# DNVT_box4rt.net
KiCad netlist of a schematic drawn in EAGLE
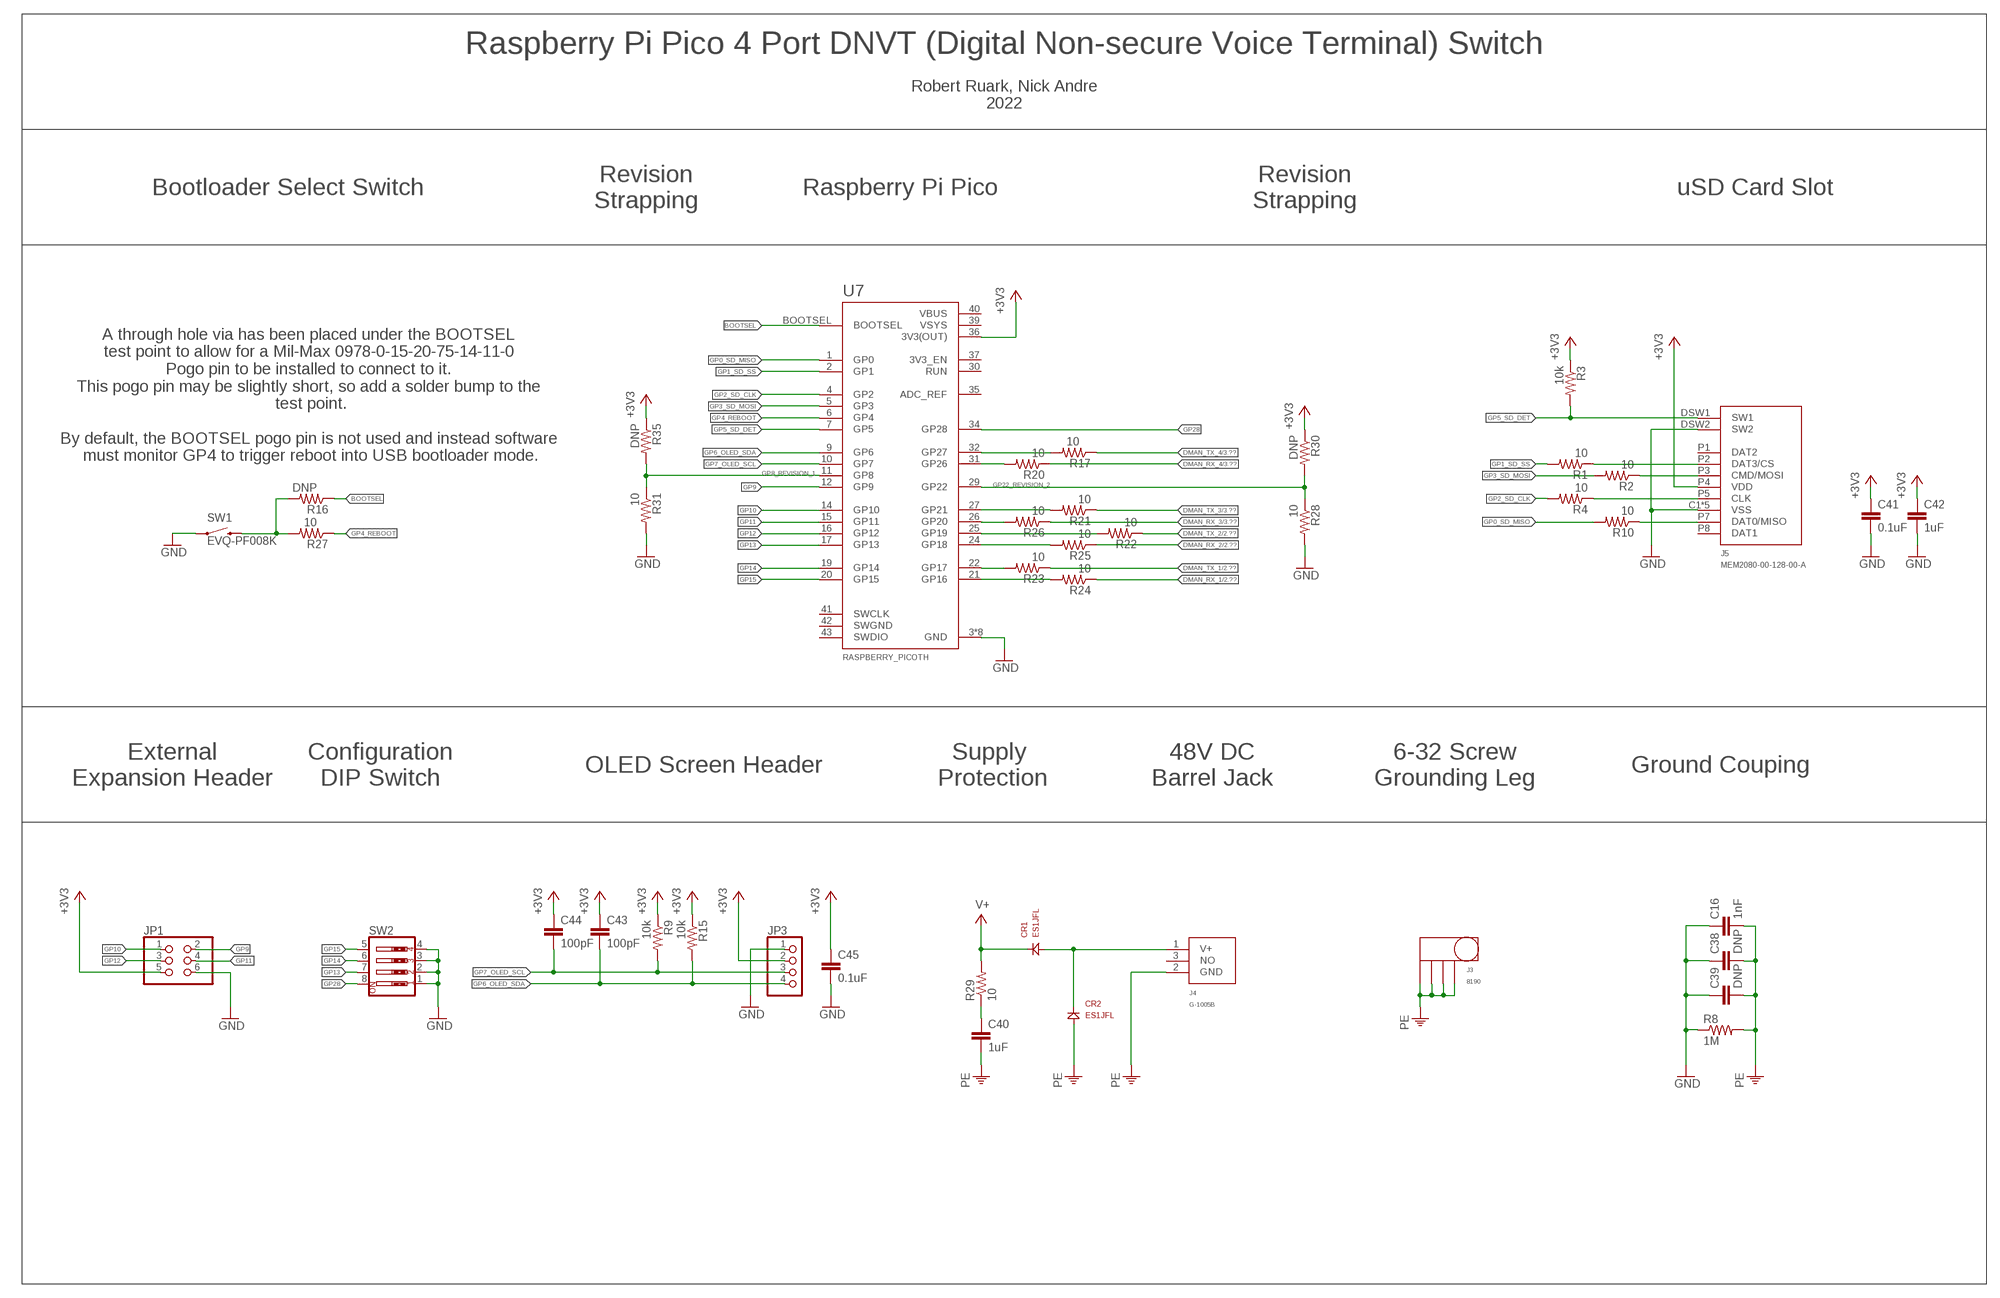
[diagram p0: schematic, sheet 1]
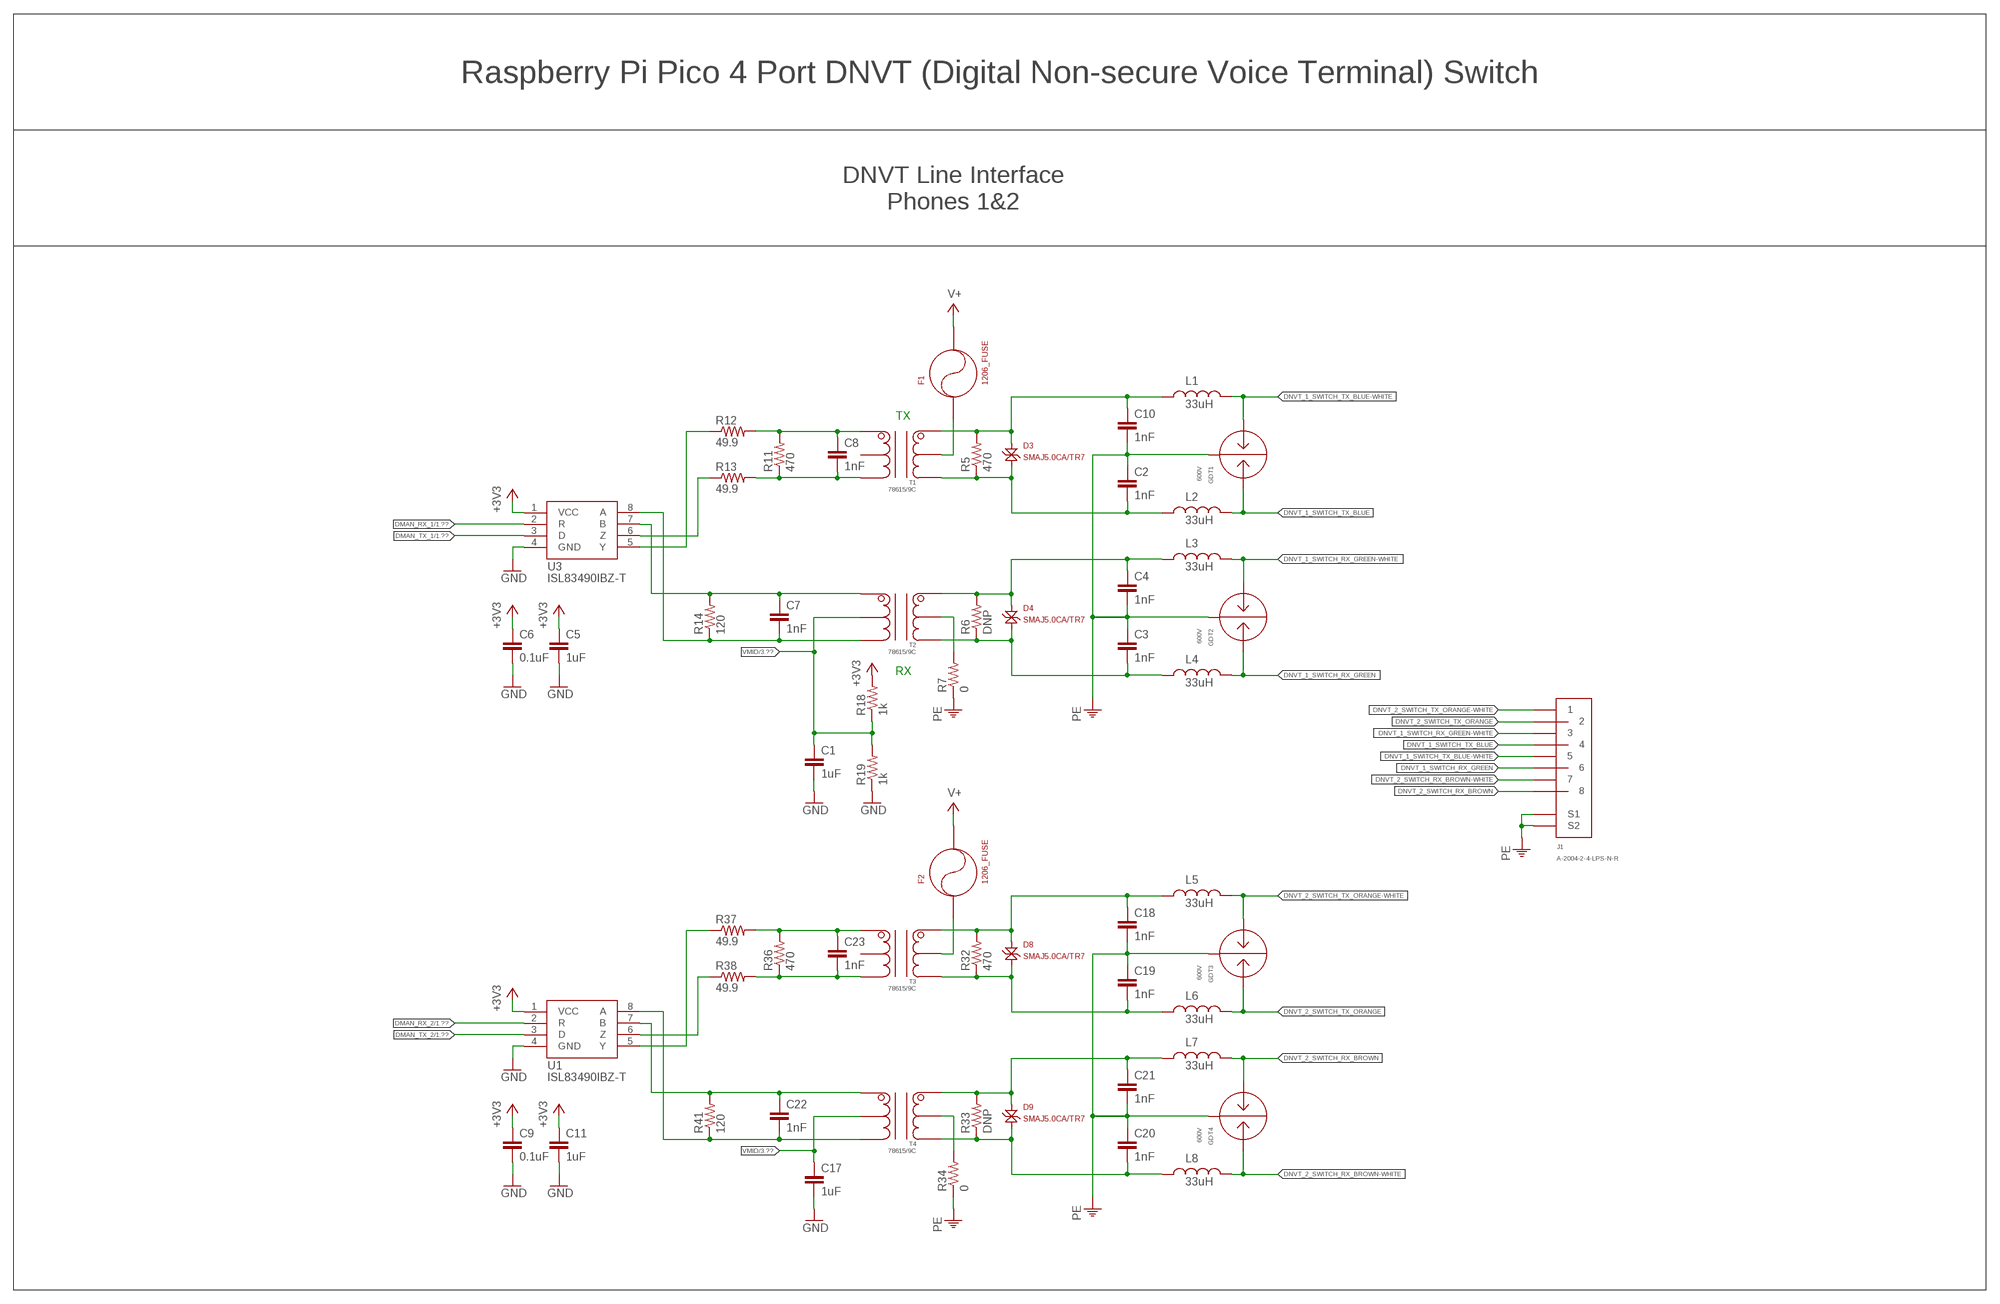
[diagram p1: schematic, sheet 2]
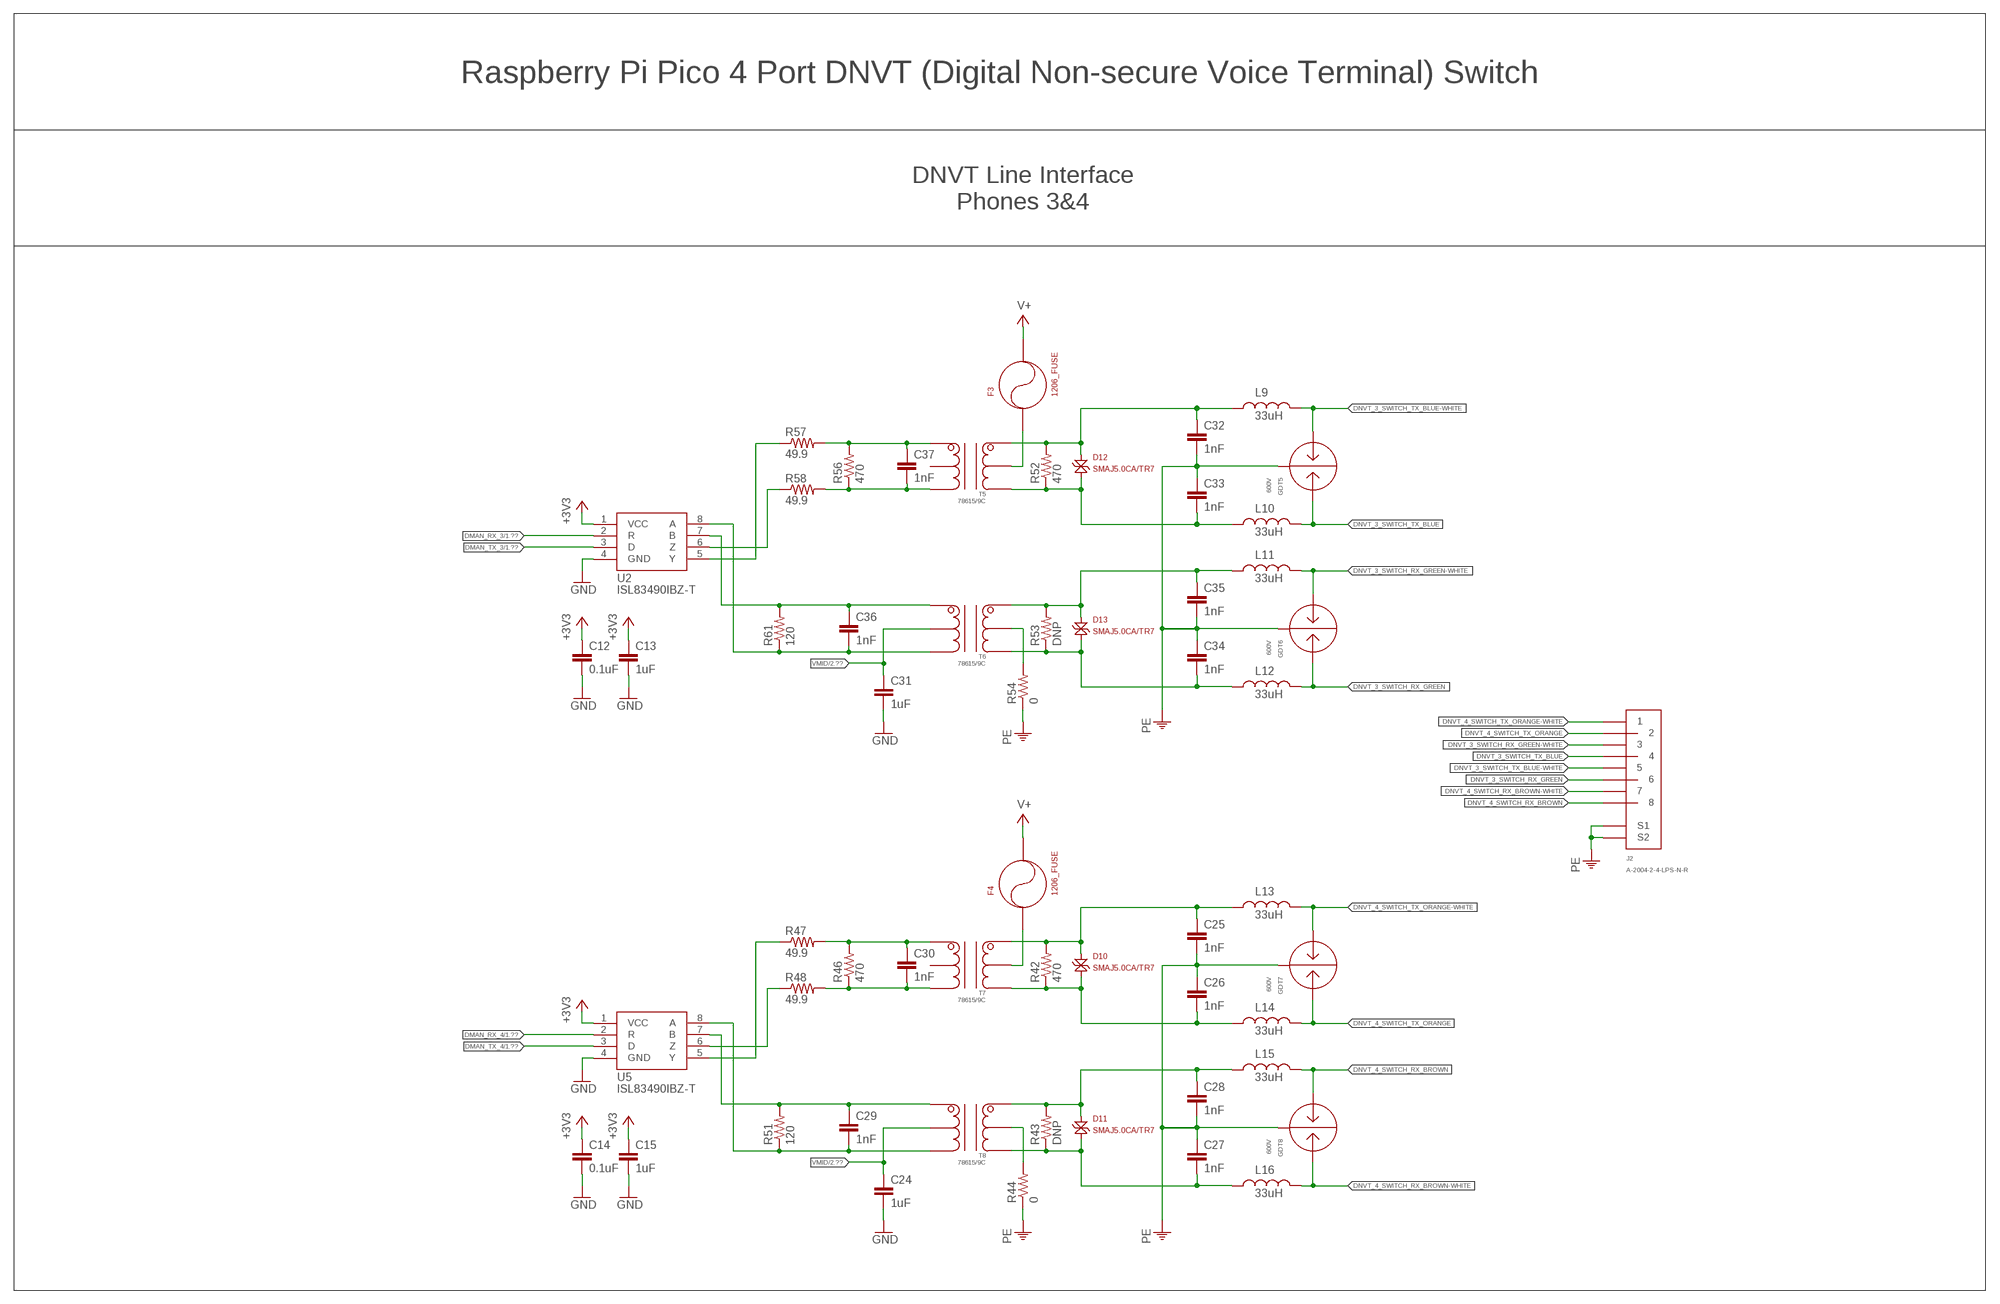
[diagram p2: schematic, sheet 3]

(export (version "E")
  (design (tool "Eeschema 10.0.6"))
  (components
    (comp (ref "C1")
      (value "1uF")
      (footprint "eagle-import:0805")
      (libsource (lib "eagle-import") (part "0805_CAPACITOR"))
    )
    (comp (ref "C2")
      (value "1nF")
      (footprint "eagle-import:0805")
      (libsource (lib "eagle-import") (part "0805_CAPACITOR"))
    )
    (comp (ref "C3")
      (value "1nF")
      (footprint "eagle-import:0805")
      (libsource (lib "eagle-import") (part "0805_CAPACITOR"))
    )
    (comp (ref "C4")
      (value "1nF")
      (footprint "eagle-import:0805")
      (libsource (lib "eagle-import") (part "0805_CAPACITOR"))
    )
    (comp (ref "C5")
      (value "1uF")
      (footprint "eagle-import:0805")
      (libsource (lib "eagle-import") (part "0805_CAPACITOR"))
    )
    (comp (ref "C6")
      (value "0.1uF")
      (footprint "eagle-import:0603")
      (libsource (lib "eagle-import") (part "0603_CAPACITOR"))
    )
    (comp (ref "C7")
      (value "1nF")
      (footprint "eagle-import:0805")
      (libsource (lib "eagle-import") (part "0805_CAPACITOR"))
    )
    (comp (ref "C8")
      (value "1nF")
      (footprint "eagle-import:0805")
      (libsource (lib "eagle-import") (part "0805_CAPACITOR"))
    )
    (comp (ref "C9")
      (value "0.1uF")
      (footprint "eagle-import:0603")
      (libsource (lib "eagle-import") (part "0603_CAPACITOR"))
    )
    (comp (ref "C10")
      (value "1nF")
      (footprint "eagle-import:0805")
      (libsource (lib "eagle-import") (part "0805_CAPACITOR"))
    )
    (comp (ref "C11")
      (value "1uF")
      (footprint "eagle-import:0805")
      (libsource (lib "eagle-import") (part "0805_CAPACITOR"))
    )
    (comp (ref "C17")
      (value "1uF")
      (footprint "eagle-import:0805")
      (libsource (lib "eagle-import") (part "0805_CAPACITOR"))
    )
    (comp (ref "C18")
      (value "1nF")
      (footprint "eagle-import:0805")
      (libsource (lib "eagle-import") (part "0805_CAPACITOR"))
    )
    (comp (ref "C19")
      (value "1nF")
      (footprint "eagle-import:0805")
      (libsource (lib "eagle-import") (part "0805_CAPACITOR"))
    )
    (comp (ref "C20")
      (value "1nF")
      (footprint "eagle-import:0805")
      (libsource (lib "eagle-import") (part "0805_CAPACITOR"))
    )
    (comp (ref "C21")
      (value "1nF")
      (footprint "eagle-import:0805")
      (libsource (lib "eagle-import") (part "0805_CAPACITOR"))
    )
    (comp (ref "C22")
      (value "1nF")
      (footprint "eagle-import:0805")
      (libsource (lib "eagle-import") (part "0805_CAPACITOR"))
    )
    (comp (ref "C23")
      (value "1nF")
      (footprint "eagle-import:0805")
      (libsource (lib "eagle-import") (part "0805_CAPACITOR"))
    )
    (comp (ref "D3")
      (value "SMAJ5.0CA/TR7")
      (footprint "eagle-import:DO-214AC_NO_POL")
      (libsource (lib "eagle-import") (part "SMAJ5.0CA/TR7"))
    )
    (comp (ref "D4")
      (value "SMAJ5.0CA/TR7")
      (footprint "eagle-import:DO-214AC_NO_POL")
      (libsource (lib "eagle-import") (part "SMAJ5.0CA/TR7"))
    )
    (comp (ref "D8")
      (value "SMAJ5.0CA/TR7")
      (footprint "eagle-import:DO-214AC_NO_POL")
      (libsource (lib "eagle-import") (part "SMAJ5.0CA/TR7"))
    )
    (comp (ref "D9")
      (value "SMAJ5.0CA/TR7")
      (footprint "eagle-import:DO-214AC_NO_POL")
      (libsource (lib "eagle-import") (part "SMAJ5.0CA/TR7"))
    )
    (comp (ref "F1")
      (value "1206_FUSE")
      (footprint "eagle-import:1206")
      (libsource (lib "eagle-import") (part "1206_FUSE"))
    )
    (comp (ref "F2")
      (value "1206_FUSE")
      (footprint "eagle-import:1206")
      (libsource (lib "eagle-import") (part "1206_FUSE"))
    )
    (comp (ref "GDT1")
      (value "600V")
      (footprint "eagle-import:2036_GDT")
      (fields (field (name "PARTNO") "2036-60-SM-RPLFCT-ND"))
      (libsource (lib "eagle-import") (part "2036-60-SM-RPLF"))
    )
    (comp (ref "GDT2")
      (value "600V")
      (footprint "eagle-import:2036_GDT")
      (fields (field (name "PARTNO") "2036-60-SM-RPLFCT-ND"))
      (libsource (lib "eagle-import") (part "2036-60-SM-RPLF"))
    )
    (comp (ref "GDT3")
      (value "600V")
      (footprint "eagle-import:2036_GDT")
      (fields (field (name "PARTNO") "2036-60-SM-RPLFCT-ND"))
      (libsource (lib "eagle-import") (part "2036-60-SM-RPLF"))
    )
    (comp (ref "GDT4")
      (value "600V")
      (footprint "eagle-import:2036_GDT")
      (fields (field (name "PARTNO") "2036-60-SM-RPLFCT-ND"))
      (libsource (lib "eagle-import") (part "2036-60-SM-RPLF"))
    )
    (comp (ref "J1")
      (value "A-2004-2-4-LPS-N-R")
      (footprint "eagle-import:A-2004-2-4-LPS-N-R")
      (fields (field (name "PARTNO") "AE10387-ND"))
      (libsource (lib "eagle-import") (part "A-2004-2-4-LPS-N-R"))
    )
    (comp (ref "L1")
      (value "33uH")
      (footprint "eagle-import:SDR0403")
      (fields (field (name "PARTNO") "SDR0403-330KLCT-ND"))
      (libsource (lib "eagle-import") (part "SDR0403-330KL"))
    )
    (comp (ref "L2")
      (value "33uH")
      (footprint "eagle-import:SDR0403")
      (fields (field (name "PARTNO") "SDR0403-330KLCT-ND"))
      (libsource (lib "eagle-import") (part "SDR0403-330KL"))
    )
    (comp (ref "L3")
      (value "33uH")
      (footprint "eagle-import:SDR0403")
      (fields (field (name "PARTNO") "SDR0403-330KLCT-ND"))
      (libsource (lib "eagle-import") (part "SDR0403-330KL"))
    )
    (comp (ref "L4")
      (value "33uH")
      (footprint "eagle-import:SDR0403")
      (fields (field (name "PARTNO") "SDR0403-330KLCT-ND"))
      (libsource (lib "eagle-import") (part "SDR0403-330KL"))
    )
    (comp (ref "L5")
      (value "33uH")
      (footprint "eagle-import:SDR0403")
      (fields (field (name "PARTNO") "SDR0403-330KLCT-ND"))
      (libsource (lib "eagle-import") (part "SDR0403-330KL"))
    )
    (comp (ref "L6")
      (value "33uH")
      (footprint "eagle-import:SDR0403")
      (fields (field (name "PARTNO") "SDR0403-330KLCT-ND"))
      (libsource (lib "eagle-import") (part "SDR0403-330KL"))
    )
    (comp (ref "L7")
      (value "33uH")
      (footprint "eagle-import:SDR0403")
      (fields (field (name "PARTNO") "SDR0403-330KLCT-ND"))
      (libsource (lib "eagle-import") (part "SDR0403-330KL"))
    )
    (comp (ref "L8")
      (value "33uH")
      (footprint "eagle-import:SDR0403")
      (fields (field (name "PARTNO") "SDR0403-330KLCT-ND"))
      (libsource (lib "eagle-import") (part "SDR0403-330KL"))
    )
    (comp (ref "R5")
      (value "470")
      (footprint "eagle-import:R0805")
      (libsource (lib "eagle-import") (part "R-US_R0805"))
    )
    (comp (ref "R6")
      (value "DNP")
      (footprint "eagle-import:R0805")
      (libsource (lib "eagle-import") (part "R-US_R0805"))
    )
    (comp (ref "R7")
      (value "0")
      (footprint "eagle-import:R0805")
      (libsource (lib "eagle-import") (part "R-US_R0805"))
    )
    (comp (ref "R11")
      (value "470")
      (footprint "eagle-import:R0805")
      (libsource (lib "eagle-import") (part "R-US_R0805"))
    )
    (comp (ref "R12")
      (value "49.9")
      (footprint "eagle-import:R0805")
      (libsource (lib "eagle-import") (part "R-US_R0805"))
    )
    (comp (ref "R13")
      (value "49.9")
      (footprint "eagle-import:R0805")
      (libsource (lib "eagle-import") (part "R-US_R0805"))
    )
    (comp (ref "R14")
      (value "120")
      (footprint "eagle-import:1206")
      (libsource (lib "eagle-import") (part "1206_RESISTOR"))
    )
    (comp (ref "R18")
      (value "1k")
      (footprint "eagle-import:0603")
      (libsource (lib "eagle-import") (part "0603_RESISTOR"))
    )
    (comp (ref "R19")
      (value "1k")
      (footprint "eagle-import:0603")
      (libsource (lib "eagle-import") (part "0603_RESISTOR"))
    )
    (comp (ref "R32")
      (value "470")
      (footprint "eagle-import:R0805")
      (libsource (lib "eagle-import") (part "R-US_R0805"))
    )
    (comp (ref "R33")
      (value "DNP")
      (footprint "eagle-import:R0805")
      (libsource (lib "eagle-import") (part "R-US_R0805"))
    )
    (comp (ref "R34")
      (value "0")
      (footprint "eagle-import:R0805")
      (libsource (lib "eagle-import") (part "R-US_R0805"))
    )
    (comp (ref "R36")
      (value "470")
      (footprint "eagle-import:R0805")
      (libsource (lib "eagle-import") (part "R-US_R0805"))
    )
    (comp (ref "R37")
      (value "49.9")
      (footprint "eagle-import:R0805")
      (libsource (lib "eagle-import") (part "R-US_R0805"))
    )
    (comp (ref "R38")
      (value "49.9")
      (footprint "eagle-import:R0805")
      (libsource (lib "eagle-import") (part "R-US_R0805"))
    )
    (comp (ref "R41")
      (value "120")
      (footprint "eagle-import:1206")
      (libsource (lib "eagle-import") (part "1206_RESISTOR"))
    )
    (comp (ref "T1")
      (value "78615/9C")
      (footprint "eagle-import:786T")
      (libsource (lib "eagle-import") (part "78615/9C"))
    )
    (comp (ref "T2")
      (value "78615/9C")
      (footprint "eagle-import:786T")
      (libsource (lib "eagle-import") (part "78615/9C"))
    )
    (comp (ref "T3")
      (value "78615/9C")
      (footprint "eagle-import:786T")
      (libsource (lib "eagle-import") (part "78615/9C"))
    )
    (comp (ref "T4")
      (value "78615/9C")
      (footprint "eagle-import:786T")
      (libsource (lib "eagle-import") (part "78615/9C"))
    )
    (comp (ref "U1")
      (value "ISL83490IBZ-T")
      (footprint "eagle-import:SOIC8")
      (fields (field (name "PARTNO") "ISL83490IBZ-TCT-ND"))
      (libsource (lib "eagle-import") (part "ISL83490IBZ-T"))
    )
    (comp (ref "U3")
      (value "ISL83490IBZ-T")
      (footprint "eagle-import:SOIC8")
      (fields (field (name "PARTNO") "ISL83490IBZ-TCT-ND"))
      (libsource (lib "eagle-import") (part "ISL83490IBZ-T"))
    )
    (comp (ref "C16")
      (value "1nF")
      (footprint "eagle-import:1206")
      (libsource (lib "eagle-import") (part "1206_CAPACITOR"))
    )
    (comp (ref "C38")
      (value "DNP")
      (footprint "eagle-import:1206")
      (libsource (lib "eagle-import") (part "1206_CAPACITOR"))
    )
    (comp (ref "C39")
      (value "DNP")
      (footprint "eagle-import:1206")
      (libsource (lib "eagle-import") (part "1206_CAPACITOR"))
    )
    (comp (ref "C40")
      (value "1uF")
      (footprint "eagle-import:1206")
      (libsource (lib "eagle-import") (part "1206_CAPACITOR"))
    )
    (comp (ref "C41")
      (value "0.1uF")
      (footprint "eagle-import:0603")
      (libsource (lib "eagle-import") (part "0603_CAPACITOR"))
    )
    (comp (ref "C42")
      (value "1uF")
      (footprint "eagle-import:0805")
      (libsource (lib "eagle-import") (part "0805_CAPACITOR"))
    )
    (comp (ref "C43")
      (value "100pF")
      (footprint "eagle-import:0603")
      (libsource (lib "eagle-import") (part "0603_CAPACITOR"))
    )
    (comp (ref "C44")
      (value "100pF")
      (footprint "eagle-import:0603")
      (libsource (lib "eagle-import") (part "0603_CAPACITOR"))
    )
    (comp (ref "C45")
      (value "0.1uF")
      (footprint "eagle-import:0603")
      (libsource (lib "eagle-import") (part "0603_CAPACITOR"))
    )
    (comp (ref "CR1")
      (value "ES1JFL")
      (footprint "eagle-import:SOD123(AK)")
      (fields (field (name "PARTNO") "ES1JFLCT-ND"))
      (libsource (lib "eagle-import") (part "ES1JFL"))
    )
    (comp (ref "CR2")
      (value "ES1JFL")
      (footprint "eagle-import:SOD123(AK)")
      (fields (field (name "PARTNO") "ES1JFLCT-ND"))
      (libsource (lib "eagle-import") (part "ES1JFL"))
    )
    (comp (ref "J3")
      (value "8190")
      (footprint "eagle-import:7781")
      (fields (field (name "PARTNO") "36-8190-ND"))
      (libsource (lib "eagle-import") (part "8190"))
    )
    (comp (ref "J4")
      (value "G-1005B")
      (footprint "eagle-import:G-1005B")
      (fields (field (name "PARTNO") "1939-G-1005B-ND"))
      (libsource (lib "eagle-import") (part "G-1005B"))
    )
    (comp (ref "J5")
      (value "MEM2080-00-128-00-A")
      (footprint "eagle-import:MEM2080")
      (fields (field (name "PARTNO") "2073-MEM2080-00-128-00-ACT-ND"))
      (libsource (lib "eagle-import") (part "MEM2080-00-128-00-A"))
    )
    (comp (ref "JP1")
      (value "PINHD-2X3/90")
      (footprint "eagle-import:2X03_90")
      (libsource (lib "eagle-import") (part "PINHD-2X3/90"))
    )
    (comp (ref "JP3")
      (value "PINHD-1X4")
      (footprint "eagle-import:1X04")
      (libsource (lib "eagle-import") (part "PINHD-1X4"))
    )
    (comp (ref "R1")
      (value "10")
      (footprint "eagle-import:0603")
      (libsource (lib "eagle-import") (part "0603_RESISTOR"))
    )
    (comp (ref "R2")
      (value "10")
      (footprint "eagle-import:0603")
      (libsource (lib "eagle-import") (part "0603_RESISTOR"))
    )
    (comp (ref "R3")
      (value "10k")
      (footprint "eagle-import:0603")
      (libsource (lib "eagle-import") (part "0603_RESISTOR"))
    )
    (comp (ref "R4")
      (value "10")
      (footprint "eagle-import:0603")
      (libsource (lib "eagle-import") (part "0603_RESISTOR"))
    )
    (comp (ref "R8")
      (value "1M")
      (footprint "eagle-import:1206")
      (libsource (lib "eagle-import") (part "1206_RESISTOR"))
    )
    (comp (ref "R9")
      (value "10k")
      (footprint "eagle-import:0603")
      (libsource (lib "eagle-import") (part "0603_RESISTOR"))
    )
    (comp (ref "R10")
      (value "10")
      (footprint "eagle-import:0603")
      (libsource (lib "eagle-import") (part "0603_RESISTOR"))
    )
    (comp (ref "R15")
      (value "10k")
      (footprint "eagle-import:0603")
      (libsource (lib "eagle-import") (part "0603_RESISTOR"))
    )
    (comp (ref "R16")
      (value "DNP")
      (footprint "eagle-import:0603")
      (libsource (lib "eagle-import") (part "0603_RESISTOR"))
    )
    (comp (ref "R17")
      (value "10")
      (footprint "eagle-import:0603")
      (libsource (lib "eagle-import") (part "0603_RESISTOR"))
    )
    (comp (ref "R20")
      (value "10")
      (footprint "eagle-import:0603")
      (libsource (lib "eagle-import") (part "0603_RESISTOR"))
    )
    (comp (ref "R21")
      (value "10")
      (footprint "eagle-import:0603")
      (libsource (lib "eagle-import") (part "0603_RESISTOR"))
    )
    (comp (ref "R22")
      (value "10")
      (footprint "eagle-import:0603")
      (libsource (lib "eagle-import") (part "0603_RESISTOR"))
    )
    (comp (ref "R23")
      (value "10")
      (footprint "eagle-import:0603")
      (libsource (lib "eagle-import") (part "0603_RESISTOR"))
    )
    (comp (ref "R24")
      (value "10")
      (footprint "eagle-import:0603")
      (libsource (lib "eagle-import") (part "0603_RESISTOR"))
    )
    (comp (ref "R25")
      (value "10")
      (footprint "eagle-import:0603")
      (libsource (lib "eagle-import") (part "0603_RESISTOR"))
    )
    (comp (ref "R26")
      (value "10")
      (footprint "eagle-import:0603")
      (libsource (lib "eagle-import") (part "0603_RESISTOR"))
    )
    (comp (ref "R27")
      (value "10")
      (footprint "eagle-import:0603")
      (libsource (lib "eagle-import") (part "0603_RESISTOR"))
    )
    (comp (ref "R28")
      (value "10")
      (footprint "eagle-import:0603")
      (libsource (lib "eagle-import") (part "0603_RESISTOR"))
    )
    (comp (ref "R29")
      (value "10")
      (footprint "eagle-import:1206")
      (libsource (lib "eagle-import") (part "1206_RESISTOR"))
    )
    (comp (ref "R30")
      (value "DNP")
      (footprint "eagle-import:0603")
      (libsource (lib "eagle-import") (part "0603_RESISTOR"))
    )
    (comp (ref "R31")
      (value "10")
      (footprint "eagle-import:0603")
      (libsource (lib "eagle-import") (part "0603_RESISTOR"))
    )
    (comp (ref "R35")
      (value "DNP")
      (footprint "eagle-import:0603")
      (libsource (lib "eagle-import") (part "0603_RESISTOR"))
    )
    (comp (ref "SW1")
      (value "EVQ-PF008K")
      (footprint "eagle-import:EVQ-PF008K")
      (fields (field (name "PARTNO") "P10880S-ND"))
      (libsource (lib "eagle-import") (part "EVQ-PF008K"))
    )
    (comp (ref "SW2")
      (value "SW_DIP-4")
      (footprint "eagle-import:EDG-04")
      (libsource (lib "eagle-import") (part "SW_DIP-4"))
    )
    (comp (ref "U7")
      (value "RASPBERRY_PICOTH")
      (footprint "eagle-import:PICO-PKG-TH")
      (libsource (lib "eagle-import") (part "RASPBERRY_PICOTH"))
    )
    (comp (ref "C12")
      (value "0.1uF")
      (footprint "eagle-import:0603")
      (libsource (lib "eagle-import") (part "0603_CAPACITOR"))
    )
    (comp (ref "C13")
      (value "1uF")
      (footprint "eagle-import:0805")
      (libsource (lib "eagle-import") (part "0805_CAPACITOR"))
    )
    (comp (ref "C14")
      (value "0.1uF")
      (footprint "eagle-import:0603")
      (libsource (lib "eagle-import") (part "0603_CAPACITOR"))
    )
    (comp (ref "C15")
      (value "1uF")
      (footprint "eagle-import:0805")
      (libsource (lib "eagle-import") (part "0805_CAPACITOR"))
    )
    (comp (ref "C24")
      (value "1uF")
      (footprint "eagle-import:0805")
      (libsource (lib "eagle-import") (part "0805_CAPACITOR"))
    )
    (comp (ref "C25")
      (value "1nF")
      (footprint "eagle-import:0805")
      (libsource (lib "eagle-import") (part "0805_CAPACITOR"))
    )
    (comp (ref "C26")
      (value "1nF")
      (footprint "eagle-import:0805")
      (libsource (lib "eagle-import") (part "0805_CAPACITOR"))
    )
    (comp (ref "C27")
      (value "1nF")
      (footprint "eagle-import:0805")
      (libsource (lib "eagle-import") (part "0805_CAPACITOR"))
    )
    (comp (ref "C28")
      (value "1nF")
      (footprint "eagle-import:0805")
      (libsource (lib "eagle-import") (part "0805_CAPACITOR"))
    )
    (comp (ref "C29")
      (value "1nF")
      (footprint "eagle-import:0805")
      (libsource (lib "eagle-import") (part "0805_CAPACITOR"))
    )
    (comp (ref "C30")
      (value "1nF")
      (footprint "eagle-import:0805")
      (libsource (lib "eagle-import") (part "0805_CAPACITOR"))
    )
    (comp (ref "C31")
      (value "1uF")
      (footprint "eagle-import:0805")
      (libsource (lib "eagle-import") (part "0805_CAPACITOR"))
    )
    (comp (ref "C32")
      (value "1nF")
      (footprint "eagle-import:0805")
      (libsource (lib "eagle-import") (part "0805_CAPACITOR"))
    )
    (comp (ref "C33")
      (value "1nF")
      (footprint "eagle-import:0805")
      (libsource (lib "eagle-import") (part "0805_CAPACITOR"))
    )
    (comp (ref "C34")
      (value "1nF")
      (footprint "eagle-import:0805")
      (libsource (lib "eagle-import") (part "0805_CAPACITOR"))
    )
    (comp (ref "C35")
      (value "1nF")
      (footprint "eagle-import:0805")
      (libsource (lib "eagle-import") (part "0805_CAPACITOR"))
    )
    (comp (ref "C36")
      (value "1nF")
      (footprint "eagle-import:0805")
      (libsource (lib "eagle-import") (part "0805_CAPACITOR"))
    )
    (comp (ref "C37")
      (value "1nF")
      (footprint "eagle-import:0805")
      (libsource (lib "eagle-import") (part "0805_CAPACITOR"))
    )
    (comp (ref "D10")
      (value "SMAJ5.0CA/TR7")
      (footprint "eagle-import:DO-214AC_NO_POL")
      (libsource (lib "eagle-import") (part "SMAJ5.0CA/TR7"))
    )
    (comp (ref "D11")
      (value "SMAJ5.0CA/TR7")
      (footprint "eagle-import:DO-214AC_NO_POL")
      (libsource (lib "eagle-import") (part "SMAJ5.0CA/TR7"))
    )
    (comp (ref "D12")
      (value "SMAJ5.0CA/TR7")
      (footprint "eagle-import:DO-214AC_NO_POL")
      (libsource (lib "eagle-import") (part "SMAJ5.0CA/TR7"))
    )
    (comp (ref "D13")
      (value "SMAJ5.0CA/TR7")
      (footprint "eagle-import:DO-214AC_NO_POL")
      (libsource (lib "eagle-import") (part "SMAJ5.0CA/TR7"))
    )
    (comp (ref "F3")
      (value "1206_FUSE")
      (footprint "eagle-import:1206")
      (libsource (lib "eagle-import") (part "1206_FUSE"))
    )
    (comp (ref "F4")
      (value "1206_FUSE")
      (footprint "eagle-import:1206")
      (libsource (lib "eagle-import") (part "1206_FUSE"))
    )
    (comp (ref "GDT5")
      (value "600V")
      (footprint "eagle-import:2036_GDT")
      (fields (field (name "PARTNO") "2036-60-SM-RPLFCT-ND"))
      (libsource (lib "eagle-import") (part "2036-60-SM-RPLF"))
    )
    (comp (ref "GDT6")
      (value "600V")
      (footprint "eagle-import:2036_GDT")
      (fields (field (name "PARTNO") "2036-60-SM-RPLFCT-ND"))
      (libsource (lib "eagle-import") (part "2036-60-SM-RPLF"))
    )
    (comp (ref "GDT7")
      (value "600V")
      (footprint "eagle-import:2036_GDT")
      (fields (field (name "PARTNO") "2036-60-SM-RPLFCT-ND"))
      (libsource (lib "eagle-import") (part "2036-60-SM-RPLF"))
    )
    (comp (ref "GDT8")
      (value "600V")
      (footprint "eagle-import:2036_GDT")
      (fields (field (name "PARTNO") "2036-60-SM-RPLFCT-ND"))
      (libsource (lib "eagle-import") (part "2036-60-SM-RPLF"))
    )
    (comp (ref "J2")
      (value "A-2004-2-4-LPS-N-R")
      (footprint "eagle-import:A-2004-2-4-LPS-N-R")
      (fields (field (name "PARTNO") "AE10387-ND"))
      (libsource (lib "eagle-import") (part "A-2004-2-4-LPS-N-R"))
    )
    (comp (ref "L9")
      (value "33uH")
      (footprint "eagle-import:SDR0403")
      (fields (field (name "PARTNO") "SDR0403-330KLCT-ND"))
      (libsource (lib "eagle-import") (part "SDR0403-330KL"))
    )
    (comp (ref "L10")
      (value "33uH")
      (footprint "eagle-import:SDR0403")
      (fields (field (name "PARTNO") "SDR0403-330KLCT-ND"))
      (libsource (lib "eagle-import") (part "SDR0403-330KL"))
    )
    (comp (ref "L11")
      (value "33uH")
      (footprint "eagle-import:SDR0403")
      (fields (field (name "PARTNO") "SDR0403-330KLCT-ND"))
      (libsource (lib "eagle-import") (part "SDR0403-330KL"))
    )
    (comp (ref "L12")
      (value "33uH")
      (footprint "eagle-import:SDR0403")
      (fields (field (name "PARTNO") "SDR0403-330KLCT-ND"))
      (libsource (lib "eagle-import") (part "SDR0403-330KL"))
    )
    (comp (ref "L13")
      (value "33uH")
      (footprint "eagle-import:SDR0403")
      (fields (field (name "PARTNO") "SDR0403-330KLCT-ND"))
      (libsource (lib "eagle-import") (part "SDR0403-330KL"))
    )
    (comp (ref "L14")
      (value "33uH")
      (footprint "eagle-import:SDR0403")
      (fields (field (name "PARTNO") "SDR0403-330KLCT-ND"))
      (libsource (lib "eagle-import") (part "SDR0403-330KL"))
    )
    (comp (ref "L15")
      (value "33uH")
      (footprint "eagle-import:SDR0403")
      (fields (field (name "PARTNO") "SDR0403-330KLCT-ND"))
      (libsource (lib "eagle-import") (part "SDR0403-330KL"))
    )
    (comp (ref "L16")
      (value "33uH")
      (footprint "eagle-import:SDR0403")
      (fields (field (name "PARTNO") "SDR0403-330KLCT-ND"))
      (libsource (lib "eagle-import") (part "SDR0403-330KL"))
    )
    (comp (ref "R42")
      (value "470")
      (footprint "eagle-import:R0805")
      (libsource (lib "eagle-import") (part "R-US_R0805"))
    )
    (comp (ref "R43")
      (value "DNP")
      (footprint "eagle-import:R0805")
      (libsource (lib "eagle-import") (part "R-US_R0805"))
    )
    (comp (ref "R44")
      (value "0")
      (footprint "eagle-import:R0805")
      (libsource (lib "eagle-import") (part "R-US_R0805"))
    )
    (comp (ref "R46")
      (value "470")
      (footprint "eagle-import:R0805")
      (libsource (lib "eagle-import") (part "R-US_R0805"))
    )
    (comp (ref "R47")
      (value "49.9")
      (footprint "eagle-import:R0805")
      (libsource (lib "eagle-import") (part "R-US_R0805"))
    )
    (comp (ref "R48")
      (value "49.9")
      (footprint "eagle-import:R0805")
      (libsource (lib "eagle-import") (part "R-US_R0805"))
    )
    (comp (ref "R51")
      (value "120")
      (footprint "eagle-import:1206")
      (libsource (lib "eagle-import") (part "1206_RESISTOR"))
    )
    (comp (ref "R52")
      (value "470")
      (footprint "eagle-import:R0805")
      (libsource (lib "eagle-import") (part "R-US_R0805"))
    )
    (comp (ref "R53")
      (value "DNP")
      (footprint "eagle-import:R0805")
      (libsource (lib "eagle-import") (part "R-US_R0805"))
    )
    (comp (ref "R54")
      (value "0")
      (footprint "eagle-import:R0805")
      (libsource (lib "eagle-import") (part "R-US_R0805"))
    )
    (comp (ref "R56")
      (value "470")
      (footprint "eagle-import:R0805")
      (libsource (lib "eagle-import") (part "R-US_R0805"))
    )
    (comp (ref "R57")
      (value "49.9")
      (footprint "eagle-import:R0805")
      (libsource (lib "eagle-import") (part "R-US_R0805"))
    )
    (comp (ref "R58")
      (value "49.9")
      (footprint "eagle-import:R0805")
      (libsource (lib "eagle-import") (part "R-US_R0805"))
    )
    (comp (ref "R61")
      (value "120")
      (footprint "eagle-import:1206")
      (libsource (lib "eagle-import") (part "1206_RESISTOR"))
    )
    (comp (ref "T5")
      (value "78615/9C")
      (footprint "eagle-import:786T")
      (libsource (lib "eagle-import") (part "78615/9C"))
    )
    (comp (ref "T6")
      (value "78615/9C")
      (footprint "eagle-import:786T")
      (libsource (lib "eagle-import") (part "78615/9C"))
    )
    (comp (ref "T7")
      (value "78615/9C")
      (footprint "eagle-import:786T")
      (libsource (lib "eagle-import") (part "78615/9C"))
    )
    (comp (ref "T8")
      (value "78615/9C")
      (footprint "eagle-import:786T")
      (libsource (lib "eagle-import") (part "78615/9C"))
    )
    (comp (ref "U2")
      (value "ISL83490IBZ-T")
      (footprint "eagle-import:SOIC8")
      (fields (field (name "PARTNO") "ISL83490IBZ-TCT-ND"))
      (libsource (lib "eagle-import") (part "ISL83490IBZ-T"))
    )
    (comp (ref "U5")
      (value "ISL83490IBZ-T")
      (footprint "eagle-import:SOIC8")
      (fields (field (name "PARTNO") "ISL83490IBZ-TCT-ND"))
      (libsource (lib "eagle-import") (part "ISL83490IBZ-T"))
    )
  )
  (nets
    (net (code "1") (name "+3V3") (class "Default")
      (node (ref "C11") (pin "1") (pinfunction "1_1") (pintype "passive"))
      (node (ref "C12") (pin "1") (pinfunction "1_1") (pintype "passive"))
      (node (ref "C13") (pin "1") (pinfunction "1_1") (pintype "passive"))
      (node (ref "C14") (pin "1") (pinfunction "1_1") (pintype "passive"))
      (node (ref "C15") (pin "1") (pinfunction "1_1") (pintype "passive"))
      (node (ref "C41") (pin "1") (pinfunction "1_1") (pintype "passive"))
      (node (ref "C42") (pin "1") (pinfunction "1_1") (pintype "passive"))
      (node (ref "C43") (pin "1") (pinfunction "1_1") (pintype "passive"))
      (node (ref "C44") (pin "1") (pinfunction "1_1") (pintype "passive"))
      (node (ref "C45") (pin "1") (pinfunction "1_1") (pintype "passive"))
      (node (ref "C5") (pin "1") (pinfunction "1_1") (pintype "passive"))
      (node (ref "C6") (pin "1") (pinfunction "1_1") (pintype "passive"))
      (node (ref "C9") (pin "1") (pinfunction "1_1") (pintype "passive"))
      (node (ref "J5") (pin "P4") (pinfunction "VDD_P4") (pintype "bidirectional"))
      (node (ref "JP1") (pin "5") (pinfunction "5_5") (pintype "passive"))
      (node (ref "JP3") (pin "2") (pinfunction "2_2") (pintype "passive"))
      (node (ref "R15") (pin "1") (pinfunction "1_1") (pintype "passive"))
      (node (ref "R18") (pin "2") (pinfunction "2_2") (pintype "passive"))
      (node (ref "R3") (pin "1") (pinfunction "1_1") (pintype "passive"))
      (node (ref "R30") (pin "1") (pinfunction "1_1") (pintype "passive"))
      (node (ref "R35") (pin "1") (pinfunction "1_1") (pintype "passive"))
      (node (ref "R9") (pin "1") (pinfunction "1_1") (pintype "passive"))
      (node (ref "U1") (pin "1") (pinfunction "VCC_1") (pintype "bidirectional"))
      (node (ref "U2") (pin "1") (pinfunction "VCC_1") (pintype "bidirectional"))
      (node (ref "U3") (pin "1") (pinfunction "VCC_1") (pintype "bidirectional"))
      (node (ref "U5") (pin "1") (pinfunction "VCC_1") (pintype "bidirectional"))
      (node (ref "U7") (pin "36") (pinfunction "3V3(OUT)_36") (pintype "power_in"))
    )
    (net (code "2") (name "BOOTSEL") (class "Default")
      (node (ref "R16") (pin "1") (pinfunction "1_1") (pintype "passive"))
      (node (ref "U7") (pin "BOOTSEL") (pinfunction "BOOTSEL_BOOTSEL") (pintype "bidirectional"))
    )
    (net (code "3") (name "DMAN_RX_1") (class "Default")
      (node (ref "R24") (pin "1") (pinfunction "1_1") (pintype "passive"))
      (node (ref "U3") (pin "2") (pinfunction "R_2") (pintype "bidirectional"))
    )
    (net (code "4") (name "DMAN_RX_2") (class "Default")
      (node (ref "R25") (pin "1") (pinfunction "1_1") (pintype "passive"))
      (node (ref "U1") (pin "2") (pinfunction "R_2") (pintype "bidirectional"))
    )
    (net (code "5") (name "DMAN_RX_3") (class "Default")
      (node (ref "R26") (pin "1") (pinfunction "1_1") (pintype "passive"))
      (node (ref "U2") (pin "2") (pinfunction "R_2") (pintype "bidirectional"))
    )
    (net (code "6") (name "DMAN_RX_4") (class "Default")
      (node (ref "R20") (pin "1") (pinfunction "1_1") (pintype "passive"))
      (node (ref "U5") (pin "2") (pinfunction "R_2") (pintype "bidirectional"))
    )
    (net (code "7") (name "DMAN_TX_1") (class "Default")
      (node (ref "R23") (pin "1") (pinfunction "1_1") (pintype "passive"))
      (node (ref "U3") (pin "3") (pinfunction "D_3") (pintype "bidirectional"))
    )
    (net (code "8") (name "DMAN_TX_2") (class "Default")
      (node (ref "R22") (pin "1") (pinfunction "1_1") (pintype "passive"))
      (node (ref "U1") (pin "3") (pinfunction "D_3") (pintype "bidirectional"))
    )
    (net (code "9") (name "DMAN_TX_3") (class "Default")
      (node (ref "R21") (pin "1") (pinfunction "1_1") (pintype "passive"))
      (node (ref "U2") (pin "3") (pinfunction "D_3") (pintype "bidirectional"))
    )
    (net (code "10") (name "DMAN_TX_4") (class "Default")
      (node (ref "R17") (pin "1") (pinfunction "1_1") (pintype "passive"))
      (node (ref "U5") (pin "3") (pinfunction "D_3") (pintype "bidirectional"))
    )
    (net (code "11") (name "DNVT_1_SWITCH_RX_GREEN") (class "Default")
      (node (ref "GDT2") (pin "L2") (pinfunction "L2_L2") (pintype "bidirectional"))
      (node (ref "J1") (pin "6") (pinfunction "6_6") (pintype "bidirectional"))
      (node (ref "L4") (pin "2") (pinfunction "P$2_2") (pintype "bidirectional"))
    )
    (net (code "12") (name "DNVT_1_SWITCH_RX_GREEN-WHITE") (class "Default")
      (node (ref "GDT2") (pin "L1") (pinfunction "L1_L1") (pintype "bidirectional"))
      (node (ref "J1") (pin "3") (pinfunction "3_3") (pintype "bidirectional"))
      (node (ref "L3") (pin "2") (pinfunction "P$2_2") (pintype "bidirectional"))
    )
    (net (code "13") (name "DNVT_1_SWITCH_TX_BLUE") (class "Default")
      (node (ref "GDT1") (pin "L2") (pinfunction "L2_L2") (pintype "bidirectional"))
      (node (ref "J1") (pin "4") (pinfunction "4_4") (pintype "bidirectional"))
      (node (ref "L2") (pin "2") (pinfunction "P$2_2") (pintype "bidirectional"))
    )
    (net (code "14") (name "DNVT_1_SWITCH_TX_BLUE-WHITE") (class "Default")
      (node (ref "GDT1") (pin "L1") (pinfunction "L1_L1") (pintype "bidirectional"))
      (node (ref "J1") (pin "5") (pinfunction "5_5") (pintype "bidirectional"))
      (node (ref "L1") (pin "2") (pinfunction "P$2_2") (pintype "bidirectional"))
    )
    (net (code "15") (name "DNVT_2_SWITCH_RX_BROWN") (class "Default")
      (node (ref "GDT4") (pin "L1") (pinfunction "L1_L1") (pintype "bidirectional"))
      (node (ref "J1") (pin "8") (pinfunction "8_8") (pintype "bidirectional"))
      (node (ref "L7") (pin "2") (pinfunction "P$2_2") (pintype "bidirectional"))
    )
    (net (code "16") (name "DNVT_2_SWITCH_RX_BROWN-WHITE") (class "Default")
      (node (ref "GDT4") (pin "L2") (pinfunction "L2_L2") (pintype "bidirectional"))
      (node (ref "J1") (pin "7") (pinfunction "7_7") (pintype "bidirectional"))
      (node (ref "L8") (pin "2") (pinfunction "P$2_2") (pintype "bidirectional"))
    )
    (net (code "17") (name "DNVT_2_SWITCH_TX_ORANGE") (class "Default")
      (node (ref "GDT3") (pin "L2") (pinfunction "L2_L2") (pintype "bidirectional"))
      (node (ref "J1") (pin "2") (pinfunction "2_2") (pintype "bidirectional"))
      (node (ref "L6") (pin "2") (pinfunction "P$2_2") (pintype "bidirectional"))
    )
    (net (code "18") (name "DNVT_2_SWITCH_TX_ORANGE-WHITE") (class "Default")
      (node (ref "GDT3") (pin "L1") (pinfunction "L1_L1") (pintype "bidirectional"))
      (node (ref "J1") (pin "1") (pinfunction "1_1") (pintype "bidirectional"))
      (node (ref "L5") (pin "2") (pinfunction "P$2_2") (pintype "bidirectional"))
    )
    (net (code "19") (name "DNVT_3_SWITCH_RX_GREEN") (class "Default")
      (node (ref "GDT6") (pin "L2") (pinfunction "L2_L2") (pintype "bidirectional"))
      (node (ref "J2") (pin "6") (pinfunction "6_6") (pintype "bidirectional"))
      (node (ref "L12") (pin "2") (pinfunction "P$2_2") (pintype "bidirectional"))
    )
    (net (code "20") (name "DNVT_3_SWITCH_RX_GREEN-WHITE") (class "Default")
      (node (ref "GDT6") (pin "L1") (pinfunction "L1_L1") (pintype "bidirectional"))
      (node (ref "J2") (pin "3") (pinfunction "3_3") (pintype "bidirectional"))
      (node (ref "L11") (pin "2") (pinfunction "P$2_2") (pintype "bidirectional"))
    )
    (net (code "21") (name "DNVT_3_SWITCH_TX_BLUE") (class "Default")
      (node (ref "GDT5") (pin "L2") (pinfunction "L2_L2") (pintype "bidirectional"))
      (node (ref "J2") (pin "4") (pinfunction "4_4") (pintype "bidirectional"))
      (node (ref "L10") (pin "2") (pinfunction "P$2_2") (pintype "bidirectional"))
    )
    (net (code "22") (name "DNVT_3_SWITCH_TX_BLUE-WHITE") (class "Default")
      (node (ref "GDT5") (pin "L1") (pinfunction "L1_L1") (pintype "bidirectional"))
      (node (ref "J2") (pin "5") (pinfunction "5_5") (pintype "bidirectional"))
      (node (ref "L9") (pin "2") (pinfunction "P$2_2") (pintype "bidirectional"))
    )
    (net (code "23") (name "DNVT_4_SWITCH_RX_BROWN") (class "Default")
      (node (ref "GDT8") (pin "L1") (pinfunction "L1_L1") (pintype "bidirectional"))
      (node (ref "J2") (pin "8") (pinfunction "8_8") (pintype "bidirectional"))
      (node (ref "L15") (pin "2") (pinfunction "P$2_2") (pintype "bidirectional"))
    )
    (net (code "24") (name "DNVT_4_SWITCH_RX_BROWN-WHITE") (class "Default")
      (node (ref "GDT8") (pin "L2") (pinfunction "L2_L2") (pintype "bidirectional"))
      (node (ref "J2") (pin "7") (pinfunction "7_7") (pintype "bidirectional"))
      (node (ref "L16") (pin "2") (pinfunction "P$2_2") (pintype "bidirectional"))
    )
    (net (code "25") (name "DNVT_4_SWITCH_TX_ORANGE") (class "Default")
      (node (ref "GDT7") (pin "L2") (pinfunction "L2_L2") (pintype "bidirectional"))
      (node (ref "J2") (pin "2") (pinfunction "2_2") (pintype "bidirectional"))
      (node (ref "L14") (pin "2") (pinfunction "P$2_2") (pintype "bidirectional"))
    )
    (net (code "26") (name "DNVT_4_SWITCH_TX_ORANGE-WHITE") (class "Default")
      (node (ref "GDT7") (pin "L1") (pinfunction "L1_L1") (pintype "bidirectional"))
      (node (ref "J2") (pin "1") (pinfunction "1_1") (pintype "bidirectional"))
      (node (ref "L13") (pin "2") (pinfunction "P$2_2") (pintype "bidirectional"))
    )
    (net (code "27") (name "GND") (class "Default")
      (node (ref "C1") (pin "2") (pinfunction "2_2") (pintype "passive"))
      (node (ref "C11") (pin "2") (pinfunction "2_2") (pintype "passive"))
      (node (ref "C12") (pin "2") (pinfunction "2_2") (pintype "passive"))
      (node (ref "C13") (pin "2") (pinfunction "2_2") (pintype "passive"))
      (node (ref "C14") (pin "2") (pinfunction "2_2") (pintype "passive"))
      (node (ref "C15") (pin "2") (pinfunction "2_2") (pintype "passive"))
      (node (ref "C16") (pin "1") (pinfunction "1_1") (pintype "passive"))
      (node (ref "C17") (pin "2") (pinfunction "2_2") (pintype "passive"))
      (node (ref "C24") (pin "2") (pinfunction "2_2") (pintype "passive"))
      (node (ref "C31") (pin "2") (pinfunction "2_2") (pintype "passive"))
      (node (ref "C38") (pin "1") (pinfunction "1_1") (pintype "passive"))
      (node (ref "C39") (pin "1") (pinfunction "1_1") (pintype "passive"))
      (node (ref "C41") (pin "2") (pinfunction "2_2") (pintype "passive"))
      (node (ref "C42") (pin "2") (pinfunction "2_2") (pintype "passive"))
      (node (ref "C45") (pin "2") (pinfunction "2_2") (pintype "passive"))
      (node (ref "C5") (pin "2") (pinfunction "2_2") (pintype "passive"))
      (node (ref "C6") (pin "2") (pinfunction "2_2") (pintype "passive"))
      (node (ref "C9") (pin "2") (pinfunction "2_2") (pintype "passive"))
      (node (ref "J5") (pin "C1") (pinfunction "VSS_C1") (pintype "bidirectional"))
      (node (ref "J5") (pin "C2") (pinfunction "VSS_C2") (pintype "bidirectional"))
      (node (ref "J5") (pin "C3") (pinfunction "VSS_C3") (pintype "bidirectional"))
      (node (ref "J5") (pin "C4") (pinfunction "VSS_C4") (pintype "bidirectional"))
      (node (ref "J5") (pin "DSW2") (pinfunction "SW2_DSW2") (pintype "bidirectional"))
      (node (ref "J5") (pin "P6") (pinfunction "VSS_P6") (pintype "bidirectional"))
      (node (ref "JP1") (pin "6") (pinfunction "6_6") (pintype "passive"))
      (node (ref "JP3") (pin "1") (pinfunction "1_1") (pintype "passive"))
      (node (ref "R19") (pin "1") (pinfunction "1_1") (pintype "passive"))
      (node (ref "R28") (pin "2") (pinfunction "2_2") (pintype "passive"))
      (node (ref "R31") (pin "2") (pinfunction "2_2") (pintype "passive"))
      (node (ref "R8") (pin "1") (pinfunction "1_1") (pintype "passive"))
      (node (ref "SW1") (pin "S1") (pinfunction "1_S1") (pintype "passive"))
      (node (ref "SW2") (pin "1") (pinfunction "1_1") (pintype "passive"))
      (node (ref "SW2") (pin "2") (pinfunction "2_2") (pintype "passive"))
      (node (ref "SW2") (pin "3") (pinfunction "3_3") (pintype "passive"))
      (node (ref "SW2") (pin "4") (pinfunction "4_4") (pintype "passive"))
      (node (ref "U1") (pin "4") (pinfunction "GND_4") (pintype "bidirectional"))
      (node (ref "U2") (pin "4") (pinfunction "GND_4") (pintype "bidirectional"))
      (node (ref "U3") (pin "4") (pinfunction "GND_4") (pintype "bidirectional"))
      (node (ref "U5") (pin "4") (pinfunction "GND_4") (pintype "bidirectional"))
      (node (ref "U7") (pin "13") (pinfunction "GND_13") (pintype "power_in"))
      (node (ref "U7") (pin "18") (pinfunction "GND_18") (pintype "power_in"))
      (node (ref "U7") (pin "23") (pinfunction "GND_23") (pintype "power_in"))
      (node (ref "U7") (pin "28") (pinfunction "GND_28") (pintype "power_in"))
      (node (ref "U7") (pin "3") (pinfunction "GND_3") (pintype "power_in"))
      (node (ref "U7") (pin "33") (pinfunction "GND_33") (pintype "power_in"))
      (node (ref "U7") (pin "38") (pinfunction "GND_38") (pintype "power_in"))
      (node (ref "U7") (pin "8") (pinfunction "GND_8") (pintype "power_in"))
    )
    (net (code "28") (name "GP0_SD_MISO") (class "Default")
      (node (ref "R10") (pin "2") (pinfunction "2_2") (pintype "passive"))
      (node (ref "U7") (pin "1") (pinfunction "GP0_1") (pintype "bidirectional"))
    )
    (net (code "29") (name "GP1_SD_SS") (class "Default")
      (node (ref "R1") (pin "2") (pinfunction "2_2") (pintype "passive"))
      (node (ref "U7") (pin "2") (pinfunction "GP1_2") (pintype "bidirectional"))
    )
    (net (code "30") (name "GP2_SD_CLK") (class "Default")
      (node (ref "R4") (pin "2") (pinfunction "2_2") (pintype "passive"))
      (node (ref "U7") (pin "4") (pinfunction "GP2_4") (pintype "bidirectional"))
    )
    (net (code "31") (name "GP3_SD_MOSI") (class "Default")
      (node (ref "R2") (pin "2") (pinfunction "2_2") (pintype "passive"))
      (node (ref "U7") (pin "5") (pinfunction "GP3_5") (pintype "bidirectional"))
    )
    (net (code "32") (name "GP4_REBOOT") (class "Default")
      (node (ref "R27") (pin "1") (pinfunction "1_1") (pintype "passive"))
      (node (ref "U7") (pin "6") (pinfunction "GP4_6") (pintype "bidirectional"))
    )
    (net (code "33") (name "GP5_SD_DET") (class "Default")
      (node (ref "J5") (pin "DSW1") (pinfunction "SW1_DSW1") (pintype "bidirectional"))
      (node (ref "R3") (pin "2") (pinfunction "2_2") (pintype "passive"))
      (node (ref "U7") (pin "7") (pinfunction "GP5_7") (pintype "bidirectional"))
    )
    (net (code "34") (name "GP6_OLED_SDA") (class "Default")
      (node (ref "C43") (pin "2") (pinfunction "2_2") (pintype "passive"))
      (node (ref "JP3") (pin "4") (pinfunction "4_4") (pintype "passive"))
      (node (ref "R15") (pin "2") (pinfunction "2_2") (pintype "passive"))
      (node (ref "U7") (pin "9") (pinfunction "GP6_9") (pintype "bidirectional"))
    )
    (net (code "35") (name "GP7_OLED_SCL") (class "Default")
      (node (ref "C44") (pin "2") (pinfunction "2_2") (pintype "passive"))
      (node (ref "JP3") (pin "3") (pinfunction "3_3") (pintype "passive"))
      (node (ref "R9") (pin "2") (pinfunction "2_2") (pintype "passive"))
      (node (ref "U7") (pin "10") (pinfunction "GP7_10") (pintype "bidirectional"))
    )
    (net (code "36") (name "GP8_REVISION_1") (class "Default")
      (node (ref "R31") (pin "1") (pinfunction "1_1") (pintype "passive"))
      (node (ref "R35") (pin "2") (pinfunction "2_2") (pintype "passive"))
      (node (ref "U7") (pin "11") (pinfunction "GP8_11") (pintype "bidirectional"))
    )
    (net (code "37") (name "GP9") (class "Default")
      (node (ref "JP1") (pin "2") (pinfunction "2_2") (pintype "passive"))
      (node (ref "U7") (pin "12") (pinfunction "GP9_12") (pintype "bidirectional"))
    )
    (net (code "38") (name "GP10") (class "Default")
      (node (ref "JP1") (pin "1") (pinfunction "1_1") (pintype "passive"))
      (node (ref "U7") (pin "14") (pinfunction "GP10_14") (pintype "bidirectional"))
    )
    (net (code "39") (name "GP11") (class "Default")
      (node (ref "JP1") (pin "4") (pinfunction "4_4") (pintype "passive"))
      (node (ref "U7") (pin "15") (pinfunction "GP11_15") (pintype "bidirectional"))
    )
    (net (code "40") (name "GP12") (class "Default")
      (node (ref "JP1") (pin "3") (pinfunction "3_3") (pintype "passive"))
      (node (ref "U7") (pin "16") (pinfunction "GP12_16") (pintype "bidirectional"))
    )
    (net (code "41") (name "GP13") (class "Default")
      (node (ref "SW2") (pin "7") (pinfunction "7_7") (pintype "passive"))
      (node (ref "U7") (pin "17") (pinfunction "GP13_17") (pintype "bidirectional"))
    )
    (net (code "42") (name "GP14") (class "Default")
      (node (ref "SW2") (pin "6") (pinfunction "6_6") (pintype "passive"))
      (node (ref "U7") (pin "19") (pinfunction "GP14_19") (pintype "bidirectional"))
    )
    (net (code "43") (name "GP15") (class "Default")
      (node (ref "SW2") (pin "5") (pinfunction "5_5") (pintype "passive"))
      (node (ref "U7") (pin "20") (pinfunction "GP15_20") (pintype "bidirectional"))
    )
    (net (code "44") (name "GP22_REVISION_2") (class "Default")
      (node (ref "R28") (pin "1") (pinfunction "1_1") (pintype "passive"))
      (node (ref "R30") (pin "2") (pinfunction "2_2") (pintype "passive"))
      (node (ref "U7") (pin "29") (pinfunction "GP22_29") (pintype "bidirectional"))
    )
    (net (code "45") (name "GP28") (class "Default")
      (node (ref "SW2") (pin "8") (pinfunction "8_8") (pintype "passive"))
      (node (ref "U7") (pin "34") (pinfunction "GP28_34") (pintype "bidirectional"))
    )
    (net (code "46") (name "Net-(C8-Pad1)") (class "Default")
      (node (ref "C8") (pin "1") (pinfunction "1_1") (pintype "passive"))
      (node (ref "R11") (pin "2") (pinfunction "2_2") (pintype "passive"))
      (node (ref "R12") (pin "2") (pinfunction "2_2") (pintype "passive"))
      (node (ref "T1") (pin "6") (pinfunction "6_6") (pintype "bidirectional"))
    )
    (net (code "47") (name "Net-(C8-Pad2)") (class "Default")
      (node (ref "C8") (pin "2") (pinfunction "2_2") (pintype "passive"))
      (node (ref "R11") (pin "1") (pinfunction "1_1") (pintype "passive"))
      (node (ref "R13") (pin "2") (pinfunction "2_2") (pintype "passive"))
      (node (ref "T1") (pin "4") (pinfunction "4_4") (pintype "bidirectional"))
    )
    (net (code "48") (name "Net-(C23-Pad1)") (class "Default")
      (node (ref "C23") (pin "1") (pinfunction "1_1") (pintype "passive"))
      (node (ref "R36") (pin "2") (pinfunction "2_2") (pintype "passive"))
      (node (ref "R37") (pin "2") (pinfunction "2_2") (pintype "passive"))
      (node (ref "T3") (pin "6") (pinfunction "6_6") (pintype "bidirectional"))
    )
    (net (code "49") (name "Net-(C23-Pad2)") (class "Default")
      (node (ref "C23") (pin "2") (pinfunction "2_2") (pintype "passive"))
      (node (ref "R36") (pin "1") (pinfunction "1_1") (pintype "passive"))
      (node (ref "R38") (pin "2") (pinfunction "2_2") (pintype "passive"))
      (node (ref "T3") (pin "4") (pinfunction "4_4") (pintype "bidirectional"))
    )
    (net (code "50") (name "Net-(C30-Pad1)") (class "Default")
      (node (ref "C30") (pin "1") (pinfunction "1_1") (pintype "passive"))
      (node (ref "R46") (pin "2") (pinfunction "2_2") (pintype "passive"))
      (node (ref "R47") (pin "2") (pinfunction "2_2") (pintype "passive"))
      (node (ref "T7") (pin "6") (pinfunction "6_6") (pintype "bidirectional"))
    )
    (net (code "51") (name "Net-(C30-Pad2)") (class "Default")
      (node (ref "C30") (pin "2") (pinfunction "2_2") (pintype "passive"))
      (node (ref "R46") (pin "1") (pinfunction "1_1") (pintype "passive"))
      (node (ref "R48") (pin "2") (pinfunction "2_2") (pintype "passive"))
      (node (ref "T7") (pin "4") (pinfunction "4_4") (pintype "bidirectional"))
    )
    (net (code "52") (name "Net-(C37-Pad1)") (class "Default")
      (node (ref "C37") (pin "1") (pinfunction "1_1") (pintype "passive"))
      (node (ref "R56") (pin "2") (pinfunction "2_2") (pintype "passive"))
      (node (ref "R57") (pin "2") (pinfunction "2_2") (pintype "passive"))
      (node (ref "T5") (pin "6") (pinfunction "6_6") (pintype "bidirectional"))
    )
    (net (code "53") (name "Net-(C37-Pad2)") (class "Default")
      (node (ref "C37") (pin "2") (pinfunction "2_2") (pintype "passive"))
      (node (ref "R56") (pin "1") (pinfunction "1_1") (pintype "passive"))
      (node (ref "R58") (pin "2") (pinfunction "2_2") (pintype "passive"))
      (node (ref "T5") (pin "4") (pinfunction "4_4") (pintype "bidirectional"))
    )
    (net (code "54") (name "Net-(C40-Pad1)") (class "Default")
      (node (ref "C40") (pin "1") (pinfunction "1_1") (pintype "passive"))
      (node (ref "R29") (pin "1") (pinfunction "1_1") (pintype "passive"))
    )
    (net (code "55") (name "Net-(D3-K)") (class "Default")
      (node (ref "C10") (pin "1") (pinfunction "1_1") (pintype "passive"))
      (node (ref "D3") (pin "C") (pinfunction "K_C") (pintype "bidirectional"))
      (node (ref "L1") (pin "1") (pinfunction "P$1_1") (pintype "bidirectional"))
      (node (ref "R5") (pin "2") (pinfunction "2_2") (pintype "passive"))
      (node (ref "T1") (pin "1") (pinfunction "1_1") (pintype "bidirectional"))
    )
    (net (code "56") (name "Net-(D4-K)") (class "Default")
      (node (ref "C4") (pin "1") (pinfunction "1_1") (pintype "passive"))
      (node (ref "D4") (pin "C") (pinfunction "K_C") (pintype "bidirectional"))
      (node (ref "L3") (pin "1") (pinfunction "P$1_1") (pintype "bidirectional"))
      (node (ref "R6") (pin "2") (pinfunction "2_2") (pintype "passive"))
      (node (ref "T2") (pin "1") (pinfunction "1_1") (pintype "bidirectional"))
    )
    (net (code "57") (name "Net-(D8-K)") (class "Default")
      (node (ref "C18") (pin "1") (pinfunction "1_1") (pintype "passive"))
      (node (ref "D8") (pin "C") (pinfunction "K_C") (pintype "bidirectional"))
      (node (ref "L5") (pin "1") (pinfunction "P$1_1") (pintype "bidirectional"))
      (node (ref "R32") (pin "2") (pinfunction "2_2") (pintype "passive"))
      (node (ref "T3") (pin "1") (pinfunction "1_1") (pintype "bidirectional"))
    )
    (net (code "58") (name "Net-(D9-K)") (class "Default")
      (node (ref "C21") (pin "1") (pinfunction "1_1") (pintype "passive"))
      (node (ref "D9") (pin "C") (pinfunction "K_C") (pintype "bidirectional"))
      (node (ref "L7") (pin "1") (pinfunction "P$1_1") (pintype "bidirectional"))
      (node (ref "R33") (pin "2") (pinfunction "2_2") (pintype "passive"))
      (node (ref "T4") (pin "1") (pinfunction "1_1") (pintype "bidirectional"))
    )
    (net (code "59") (name "Net-(D10-K)") (class "Default")
      (node (ref "C25") (pin "1") (pinfunction "1_1") (pintype "passive"))
      (node (ref "D10") (pin "C") (pinfunction "K_C") (pintype "bidirectional"))
      (node (ref "L13") (pin "1") (pinfunction "P$1_1") (pintype "bidirectional"))
      (node (ref "R42") (pin "2") (pinfunction "2_2") (pintype "passive"))
      (node (ref "T7") (pin "1") (pinfunction "1_1") (pintype "bidirectional"))
    )
    (net (code "60") (name "Net-(D11-K)") (class "Default")
      (node (ref "C28") (pin "1") (pinfunction "1_1") (pintype "passive"))
      (node (ref "D11") (pin "C") (pinfunction "K_C") (pintype "bidirectional"))
      (node (ref "L15") (pin "1") (pinfunction "P$1_1") (pintype "bidirectional"))
      (node (ref "R43") (pin "2") (pinfunction "2_2") (pintype "passive"))
      (node (ref "T8") (pin "1") (pinfunction "1_1") (pintype "bidirectional"))
    )
    (net (code "61") (name "Net-(D12-K)") (class "Default")
      (node (ref "C32") (pin "1") (pinfunction "1_1") (pintype "passive"))
      (node (ref "D12") (pin "C") (pinfunction "K_C") (pintype "bidirectional"))
      (node (ref "L9") (pin "1") (pinfunction "P$1_1") (pintype "bidirectional"))
      (node (ref "R52") (pin "2") (pinfunction "2_2") (pintype "passive"))
      (node (ref "T5") (pin "1") (pinfunction "1_1") (pintype "bidirectional"))
    )
    (net (code "62") (name "Net-(D13-K)") (class "Default")
      (node (ref "C35") (pin "1") (pinfunction "1_1") (pintype "passive"))
      (node (ref "D13") (pin "C") (pinfunction "K_C") (pintype "bidirectional"))
      (node (ref "L11") (pin "1") (pinfunction "P$1_1") (pintype "bidirectional"))
      (node (ref "R53") (pin "2") (pinfunction "2_2") (pintype "passive"))
      (node (ref "T6") (pin "1") (pinfunction "1_1") (pintype "bidirectional"))
    )
    (net (code "63") (name "Net-(F1-P$1)") (class "Default")
      (node (ref "F1") (pin "1") (pinfunction "P$1_1") (pintype "bidirectional"))
      (node (ref "T1") (pin "2") (pinfunction "2_2") (pintype "bidirectional"))
    )
    (net (code "64") (name "Net-(F2-P$1)") (class "Default")
      (node (ref "F2") (pin "1") (pinfunction "P$1_1") (pintype "bidirectional"))
      (node (ref "T3") (pin "2") (pinfunction "2_2") (pintype "bidirectional"))
    )
    (net (code "65") (name "Net-(F3-P$1)") (class "Default")
      (node (ref "F3") (pin "1") (pinfunction "P$1_1") (pintype "bidirectional"))
      (node (ref "T5") (pin "2") (pinfunction "2_2") (pintype "bidirectional"))
    )
    (net (code "66") (name "Net-(F4-P$1)") (class "Default")
      (node (ref "F4") (pin "1") (pinfunction "P$1_1") (pintype "bidirectional"))
      (node (ref "T7") (pin "2") (pinfunction "2_2") (pintype "bidirectional"))
    )
    (net (code "67") (name "Net-(J4-V+)") (class "Default")
      (node (ref "CR1") (pin "A") (pinfunction "A_A") (pintype "bidirectional"))
      (node (ref "CR2") (pin "K") (pinfunction "K_K") (pintype "bidirectional"))
      (node (ref "J4") (pin "1") (pinfunction "V+_1") (pintype "bidirectional"))
    )
    (net (code "68") (name "Net-(J5-CLK)") (class "Default")
      (node (ref "J5") (pin "P5") (pinfunction "CLK_P5") (pintype "bidirectional"))
      (node (ref "R4") (pin "1") (pinfunction "1_1") (pintype "passive"))
    )
    (net (code "69") (name "Net-(J5-CMD{slash}MOSI)") (class "Default")
      (node (ref "J5") (pin "P3") (pinfunction "CMD/MOSI_P3") (pintype "bidirectional"))
      (node (ref "R2") (pin "1") (pinfunction "1_1") (pintype "passive"))
    )
    (net (code "70") (name "Net-(J5-DAT0{slash}MISO)") (class "Default")
      (node (ref "J5") (pin "P7") (pinfunction "DAT0/MISO_P7") (pintype "bidirectional"))
      (node (ref "R10") (pin "1") (pinfunction "1_1") (pintype "passive"))
    )
    (net (code "71") (name "Net-(J5-DAT3{slash}CS)") (class "Default")
      (node (ref "J5") (pin "P2") (pinfunction "DAT3/CS_P2") (pintype "bidirectional"))
      (node (ref "R1") (pin "1") (pinfunction "1_1") (pintype "passive"))
    )
    (net (code "72") (name "Net-(L2-P$1)") (class "Default")
      (node (ref "C2") (pin "2") (pinfunction "2_2") (pintype "passive"))
      (node (ref "D3") (pin "A") (pinfunction "A_A") (pintype "bidirectional"))
      (node (ref "L2") (pin "1") (pinfunction "P$1_1") (pintype "bidirectional"))
      (node (ref "R5") (pin "1") (pinfunction "1_1") (pintype "passive"))
      (node (ref "T1") (pin "3") (pinfunction "3_3") (pintype "bidirectional"))
    )
    (net (code "73") (name "Net-(L4-P$1)") (class "Default")
      (node (ref "C3") (pin "2") (pinfunction "2_2") (pintype "passive"))
      (node (ref "D4") (pin "A") (pinfunction "A_A") (pintype "bidirectional"))
      (node (ref "L4") (pin "1") (pinfunction "P$1_1") (pintype "bidirectional"))
      (node (ref "R6") (pin "1") (pinfunction "1_1") (pintype "passive"))
      (node (ref "T2") (pin "3") (pinfunction "3_3") (pintype "bidirectional"))
    )
    (net (code "74") (name "Net-(L6-P$1)") (class "Default")
      (node (ref "C19") (pin "2") (pinfunction "2_2") (pintype "passive"))
      (node (ref "D8") (pin "A") (pinfunction "A_A") (pintype "bidirectional"))
      (node (ref "L6") (pin "1") (pinfunction "P$1_1") (pintype "bidirectional"))
      (node (ref "R32") (pin "1") (pinfunction "1_1") (pintype "passive"))
      (node (ref "T3") (pin "3") (pinfunction "3_3") (pintype "bidirectional"))
    )
    (net (code "75") (name "Net-(L8-P$1)") (class "Default")
      (node (ref "C20") (pin "2") (pinfunction "2_2") (pintype "passive"))
      (node (ref "D9") (pin "A") (pinfunction "A_A") (pintype "bidirectional"))
      (node (ref "L8") (pin "1") (pinfunction "P$1_1") (pintype "bidirectional"))
      (node (ref "R33") (pin "1") (pinfunction "1_1") (pintype "passive"))
      (node (ref "T4") (pin "3") (pinfunction "3_3") (pintype "bidirectional"))
    )
    (net (code "76") (name "Net-(L10-P$1)") (class "Default")
      (node (ref "C33") (pin "2") (pinfunction "2_2") (pintype "passive"))
      (node (ref "D12") (pin "A") (pinfunction "A_A") (pintype "bidirectional"))
      (node (ref "L10") (pin "1") (pinfunction "P$1_1") (pintype "bidirectional"))
      (node (ref "R52") (pin "1") (pinfunction "1_1") (pintype "passive"))
      (node (ref "T5") (pin "3") (pinfunction "3_3") (pintype "bidirectional"))
    )
    (net (code "77") (name "Net-(L12-P$1)") (class "Default")
      (node (ref "C34") (pin "2") (pinfunction "2_2") (pintype "passive"))
      (node (ref "D13") (pin "A") (pinfunction "A_A") (pintype "bidirectional"))
      (node (ref "L12") (pin "1") (pinfunction "P$1_1") (pintype "bidirectional"))
      (node (ref "R53") (pin "1") (pinfunction "1_1") (pintype "passive"))
      (node (ref "T6") (pin "3") (pinfunction "3_3") (pintype "bidirectional"))
    )
    (net (code "78") (name "Net-(L14-P$1)") (class "Default")
      (node (ref "C26") (pin "2") (pinfunction "2_2") (pintype "passive"))
      (node (ref "D10") (pin "A") (pinfunction "A_A") (pintype "bidirectional"))
      (node (ref "L14") (pin "1") (pinfunction "P$1_1") (pintype "bidirectional"))
      (node (ref "R42") (pin "1") (pinfunction "1_1") (pintype "passive"))
      (node (ref "T7") (pin "3") (pinfunction "3_3") (pintype "bidirectional"))
    )
    (net (code "79") (name "Net-(L16-P$1)") (class "Default")
      (node (ref "C27") (pin "2") (pinfunction "2_2") (pintype "passive"))
      (node (ref "D11") (pin "A") (pinfunction "A_A") (pintype "bidirectional"))
      (node (ref "L16") (pin "1") (pinfunction "P$1_1") (pintype "bidirectional"))
      (node (ref "R43") (pin "1") (pinfunction "1_1") (pintype "passive"))
      (node (ref "T8") (pin "3") (pinfunction "3_3") (pintype "bidirectional"))
    )
    (net (code "80") (name "Net-(R7-Pad2)") (class "Default")
      (node (ref "R7") (pin "2") (pinfunction "2_2") (pintype "passive"))
      (node (ref "T2") (pin "2") (pinfunction "2_2") (pintype "bidirectional"))
    )
    (net (code "81") (name "Net-(R34-Pad2)") (class "Default")
      (node (ref "R34") (pin "2") (pinfunction "2_2") (pintype "passive"))
      (node (ref "T4") (pin "2") (pinfunction "2_2") (pintype "bidirectional"))
    )
    (net (code "82") (name "Net-(R44-Pad2)") (class "Default")
      (node (ref "R44") (pin "2") (pinfunction "2_2") (pintype "passive"))
      (node (ref "T8") (pin "2") (pinfunction "2_2") (pintype "bidirectional"))
    )
    (net (code "83") (name "Net-(R54-Pad2)") (class "Default")
      (node (ref "R54") (pin "2") (pinfunction "2_2") (pintype "passive"))
      (node (ref "T6") (pin "2") (pinfunction "2_2") (pintype "bidirectional"))
    )
    (net (code "84") (name "Net-(SW1-2)") (class "Default")
      (node (ref "R16") (pin "2") (pinfunction "2_2") (pintype "passive"))
      (node (ref "R27") (pin "2") (pinfunction "2_2") (pintype "passive"))
      (node (ref "SW1") (pin "S2") (pinfunction "2_S2") (pintype "passive"))
    )
    (net (code "85") (name "Net-(U1-A)") (class "Default")
      (node (ref "C22") (pin "2") (pinfunction "2_2") (pintype "passive"))
      (node (ref "R41") (pin "1") (pinfunction "1_1") (pintype "passive"))
      (node (ref "T4") (pin "4") (pinfunction "4_4") (pintype "bidirectional"))
      (node (ref "U1") (pin "8") (pinfunction "A_8") (pintype "bidirectional"))
    )
    (net (code "86") (name "Net-(U1-B)") (class "Default")
      (node (ref "C22") (pin "1") (pinfunction "1_1") (pintype "passive"))
      (node (ref "R41") (pin "2") (pinfunction "2_2") (pintype "passive"))
      (node (ref "T4") (pin "6") (pinfunction "6_6") (pintype "bidirectional"))
      (node (ref "U1") (pin "7") (pinfunction "B_7") (pintype "bidirectional"))
    )
    (net (code "87") (name "Net-(U1-Y)") (class "Default")
      (node (ref "R37") (pin "1") (pinfunction "1_1") (pintype "passive"))
      (node (ref "U1") (pin "5") (pinfunction "Y_5") (pintype "bidirectional"))
    )
    (net (code "88") (name "Net-(U1-Z)") (class "Default")
      (node (ref "R38") (pin "1") (pinfunction "1_1") (pintype "passive"))
      (node (ref "U1") (pin "6") (pinfunction "Z_6") (pintype "bidirectional"))
    )
    (net (code "89") (name "Net-(U2-A)") (class "Default")
      (node (ref "C36") (pin "2") (pinfunction "2_2") (pintype "passive"))
      (node (ref "R61") (pin "1") (pinfunction "1_1") (pintype "passive"))
      (node (ref "T6") (pin "4") (pinfunction "4_4") (pintype "bidirectional"))
      (node (ref "U2") (pin "8") (pinfunction "A_8") (pintype "bidirectional"))
    )
    (net (code "90") (name "Net-(U2-B)") (class "Default")
      (node (ref "C36") (pin "1") (pinfunction "1_1") (pintype "passive"))
      (node (ref "R61") (pin "2") (pinfunction "2_2") (pintype "passive"))
      (node (ref "T6") (pin "6") (pinfunction "6_6") (pintype "bidirectional"))
      (node (ref "U2") (pin "7") (pinfunction "B_7") (pintype "bidirectional"))
    )
    (net (code "91") (name "Net-(U2-Y)") (class "Default")
      (node (ref "R57") (pin "1") (pinfunction "1_1") (pintype "passive"))
      (node (ref "U2") (pin "5") (pinfunction "Y_5") (pintype "bidirectional"))
    )
    (net (code "92") (name "Net-(U2-Z)") (class "Default")
      (node (ref "R58") (pin "1") (pinfunction "1_1") (pintype "passive"))
      (node (ref "U2") (pin "6") (pinfunction "Z_6") (pintype "bidirectional"))
    )
    (net (code "93") (name "Net-(U3-A)") (class "Default")
      (node (ref "C7") (pin "2") (pinfunction "2_2") (pintype "passive"))
      (node (ref "R14") (pin "1") (pinfunction "1_1") (pintype "passive"))
      (node (ref "T2") (pin "4") (pinfunction "4_4") (pintype "bidirectional"))
      (node (ref "U3") (pin "8") (pinfunction "A_8") (pintype "bidirectional"))
    )
    (net (code "94") (name "Net-(U3-B)") (class "Default")
      (node (ref "C7") (pin "1") (pinfunction "1_1") (pintype "passive"))
      (node (ref "R14") (pin "2") (pinfunction "2_2") (pintype "passive"))
      (node (ref "T2") (pin "6") (pinfunction "6_6") (pintype "bidirectional"))
      (node (ref "U3") (pin "7") (pinfunction "B_7") (pintype "bidirectional"))
    )
    (net (code "95") (name "Net-(U3-Y)") (class "Default")
      (node (ref "R12") (pin "1") (pinfunction "1_1") (pintype "passive"))
      (node (ref "U3") (pin "5") (pinfunction "Y_5") (pintype "bidirectional"))
    )
    (net (code "96") (name "Net-(U3-Z)") (class "Default")
      (node (ref "R13") (pin "1") (pinfunction "1_1") (pintype "passive"))
      (node (ref "U3") (pin "6") (pinfunction "Z_6") (pintype "bidirectional"))
    )
    (net (code "97") (name "Net-(U5-A)") (class "Default")
      (node (ref "C29") (pin "2") (pinfunction "2_2") (pintype "passive"))
      (node (ref "R51") (pin "1") (pinfunction "1_1") (pintype "passive"))
      (node (ref "T8") (pin "4") (pinfunction "4_4") (pintype "bidirectional"))
      (node (ref "U5") (pin "8") (pinfunction "A_8") (pintype "bidirectional"))
    )
    (net (code "98") (name "Net-(U5-B)") (class "Default")
      (node (ref "C29") (pin "1") (pinfunction "1_1") (pintype "passive"))
      (node (ref "R51") (pin "2") (pinfunction "2_2") (pintype "passive"))
      (node (ref "T8") (pin "6") (pinfunction "6_6") (pintype "bidirectional"))
      (node (ref "U5") (pin "7") (pinfunction "B_7") (pintype "bidirectional"))
    )
    (net (code "99") (name "Net-(U5-Y)") (class "Default")
      (node (ref "R47") (pin "1") (pinfunction "1_1") (pintype "passive"))
      (node (ref "U5") (pin "5") (pinfunction "Y_5") (pintype "bidirectional"))
    )
    (net (code "100") (name "Net-(U5-Z)") (class "Default")
      (node (ref "R48") (pin "1") (pinfunction "1_1") (pintype "passive"))
      (node (ref "U5") (pin "6") (pinfunction "Z_6") (pintype "bidirectional"))
    )
    (net (code "101") (name "Net-(U7-GP16)") (class "Default")
      (node (ref "R24") (pin "2") (pinfunction "2_2") (pintype "passive"))
      (node (ref "U7") (pin "21") (pinfunction "GP16_21") (pintype "bidirectional"))
    )
    (net (code "102") (name "Net-(U7-GP17)") (class "Default")
      (node (ref "R23") (pin "2") (pinfunction "2_2") (pintype "passive"))
      (node (ref "U7") (pin "22") (pinfunction "GP17_22") (pintype "bidirectional"))
    )
    (net (code "103") (name "Net-(U7-GP18)") (class "Default")
      (node (ref "R25") (pin "2") (pinfunction "2_2") (pintype "passive"))
      (node (ref "U7") (pin "24") (pinfunction "GP18_24") (pintype "bidirectional"))
    )
    (net (code "104") (name "Net-(U7-GP19)") (class "Default")
      (node (ref "R22") (pin "2") (pinfunction "2_2") (pintype "passive"))
      (node (ref "U7") (pin "25") (pinfunction "GP19_25") (pintype "bidirectional"))
    )
    (net (code "105") (name "Net-(U7-GP20)") (class "Default")
      (node (ref "R26") (pin "2") (pinfunction "2_2") (pintype "passive"))
      (node (ref "U7") (pin "26") (pinfunction "GP20_26") (pintype "bidirectional"))
    )
    (net (code "106") (name "Net-(U7-GP21)") (class "Default")
      (node (ref "R21") (pin "2") (pinfunction "2_2") (pintype "passive"))
      (node (ref "U7") (pin "27") (pinfunction "GP21_27") (pintype "bidirectional"))
    )
    (net (code "107") (name "Net-(U7-GP26)") (class "Default")
      (node (ref "R20") (pin "2") (pinfunction "2_2") (pintype "passive"))
      (node (ref "U7") (pin "31") (pinfunction "GP26_31") (pintype "bidirectional"))
    )
    (net (code "108") (name "Net-(U7-GP27)") (class "Default")
      (node (ref "R17") (pin "2") (pinfunction "2_2") (pintype "passive"))
      (node (ref "U7") (pin "32") (pinfunction "GP27_32") (pintype "bidirectional"))
    )
    (net (code "109") (name "PE") (class "Default")
      (node (ref "C10") (pin "2") (pinfunction "2_2") (pintype "passive"))
      (node (ref "C16") (pin "2") (pinfunction "2_2") (pintype "passive"))
      (node (ref "C18") (pin "2") (pinfunction "2_2") (pintype "passive"))
      (node (ref "C19") (pin "1") (pinfunction "1_1") (pintype "passive"))
      (node (ref "C2") (pin "1") (pinfunction "1_1") (pintype "passive"))
      (node (ref "C20") (pin "1") (pinfunction "1_1") (pintype "passive"))
      (node (ref "C21") (pin "2") (pinfunction "2_2") (pintype "passive"))
      (node (ref "C25") (pin "2") (pinfunction "2_2") (pintype "passive"))
      (node (ref "C26") (pin "1") (pinfunction "1_1") (pintype "passive"))
      (node (ref "C27") (pin "1") (pinfunction "1_1") (pintype "passive"))
      (node (ref "C28") (pin "2") (pinfunction "2_2") (pintype "passive"))
      (node (ref "C3") (pin "1") (pinfunction "1_1") (pintype "passive"))
      (node (ref "C32") (pin "2") (pinfunction "2_2") (pintype "passive"))
      (node (ref "C33") (pin "1") (pinfunction "1_1") (pintype "passive"))
      (node (ref "C34") (pin "1") (pinfunction "1_1") (pintype "passive"))
      (node (ref "C35") (pin "2") (pinfunction "2_2") (pintype "passive"))
      (node (ref "C38") (pin "2") (pinfunction "2_2") (pintype "passive"))
      (node (ref "C39") (pin "2") (pinfunction "2_2") (pintype "passive"))
      (node (ref "C4") (pin "2") (pinfunction "2_2") (pintype "passive"))
      (node (ref "C40") (pin "2") (pinfunction "2_2") (pintype "passive"))
      (node (ref "CR2") (pin "A") (pinfunction "A_A") (pintype "bidirectional"))
      (node (ref "GDT1") (pin "C") (pinfunction "C_C") (pintype "bidirectional"))
      (node (ref "GDT2") (pin "C") (pinfunction "C_C") (pintype "bidirectional"))
      (node (ref "GDT3") (pin "C") (pinfunction "C_C") (pintype "bidirectional"))
      (node (ref "GDT4") (pin "C") (pinfunction "C_C") (pintype "bidirectional"))
      (node (ref "GDT5") (pin "C") (pinfunction "C_C") (pintype "bidirectional"))
      (node (ref "GDT6") (pin "C") (pinfunction "C_C") (pintype "bidirectional"))
      (node (ref "GDT7") (pin "C") (pinfunction "C_C") (pintype "bidirectional"))
      (node (ref "GDT8") (pin "C") (pinfunction "C_C") (pintype "bidirectional"))
      (node (ref "J1") (pin "S1") (pinfunction "S1_S1") (pintype "bidirectional"))
      (node (ref "J1") (pin "S2") (pinfunction "S2_S2") (pintype "bidirectional"))
      (node (ref "J2") (pin "S1") (pinfunction "S1_S1") (pintype "bidirectional"))
      (node (ref "J2") (pin "S2") (pinfunction "S2_S2") (pintype "bidirectional"))
      (node (ref "J3") (pin "P$1") (pinfunction "P$1_P$1") (pintype "bidirectional"))
      (node (ref "J3") (pin "P$2") (pinfunction "P$2_P$2") (pintype "bidirectional"))
      (node (ref "J3") (pin "P$3") (pinfunction "P$3_P$3") (pintype "bidirectional"))
      (node (ref "J3") (pin "P$4") (pinfunction "P$4_P$4") (pintype "bidirectional"))
      (node (ref "J4") (pin "2") (pinfunction "GND_2") (pintype "bidirectional"))
      (node (ref "R34") (pin "1") (pinfunction "1_1") (pintype "passive"))
      (node (ref "R44") (pin "1") (pinfunction "1_1") (pintype "passive"))
      (node (ref "R54") (pin "1") (pinfunction "1_1") (pintype "passive"))
      (node (ref "R7") (pin "1") (pinfunction "1_1") (pintype "passive"))
      (node (ref "R8") (pin "2") (pinfunction "2_2") (pintype "passive"))
    )
    (net (code "110") (name "SWGND") (class "Default")
      (node (ref "U7") (pin "42") (pinfunction "SWGND_42") (pintype "power_in"))
    )
    (net (code "111") (name "V+") (class "Default")
      (node (ref "CR1") (pin "K") (pinfunction "K_K") (pintype "bidirectional"))
      (node (ref "F1") (pin "2") (pinfunction "P$2_2") (pintype "bidirectional"))
      (node (ref "F2") (pin "2") (pinfunction "P$2_2") (pintype "bidirectional"))
      (node (ref "F3") (pin "2") (pinfunction "P$2_2") (pintype "bidirectional"))
      (node (ref "F4") (pin "2") (pinfunction "P$2_2") (pintype "bidirectional"))
      (node (ref "R29") (pin "2") (pinfunction "2_2") (pintype "passive"))
    )
    (net (code "112") (name "VBUS") (class "Default")
      (node (ref "U7") (pin "40") (pinfunction "VBUS_40") (pintype "power_in"))
    )
    (net (code "113") (name "VMID") (class "Default")
      (node (ref "C1") (pin "1") (pinfunction "1_1") (pintype "passive"))
      (node (ref "C17") (pin "1") (pinfunction "1_1") (pintype "passive"))
      (node (ref "C24") (pin "1") (pinfunction "1_1") (pintype "passive"))
      (node (ref "C31") (pin "1") (pinfunction "1_1") (pintype "passive"))
      (node (ref "R18") (pin "1") (pinfunction "1_1") (pintype "passive"))
      (node (ref "R19") (pin "2") (pinfunction "2_2") (pintype "passive"))
      (node (ref "T2") (pin "5") (pinfunction "5_5") (pintype "bidirectional"))
      (node (ref "T4") (pin "5") (pinfunction "5_5") (pintype "bidirectional"))
      (node (ref "T6") (pin "5") (pinfunction "5_5") (pintype "bidirectional"))
      (node (ref "T8") (pin "5") (pinfunction "5_5") (pintype "bidirectional"))
    )
    (net (code "114") (name "VSYS") (class "Default")
      (node (ref "U7") (pin "39") (pinfunction "VSYS_39") (pintype "power_in"))
    )
    (net (code "115") (name "unconnected-(J4-NO-Pad3)") (class "Default")
      (node (ref "J4") (pin "3") (pinfunction "NO_3") (pintype "bidirectional"))
    )
    (net (code "116") (name "unconnected-(J5-DAT1-PadP8)") (class "Default")
      (node (ref "J5") (pin "P8") (pinfunction "DAT1_P8") (pintype "bidirectional"))
    )
    (net (code "117") (name "unconnected-(J5-DAT2-PadP1)") (class "Default")
      (node (ref "J5") (pin "P1") (pinfunction "DAT2_P1") (pintype "bidirectional"))
    )
    (net (code "118") (name "unconnected-(T1-Pad5)") (class "Default")
      (node (ref "T1") (pin "5") (pinfunction "5_5") (pintype "bidirectional"))
    )
    (net (code "119") (name "unconnected-(T3-Pad5)") (class "Default")
      (node (ref "T3") (pin "5") (pinfunction "5_5") (pintype "bidirectional"))
    )
    (net (code "120") (name "unconnected-(T5-Pad5)") (class "Default")
      (node (ref "T5") (pin "5") (pinfunction "5_5") (pintype "bidirectional"))
    )
    (net (code "121") (name "unconnected-(T7-Pad5)") (class "Default")
      (node (ref "T7") (pin "5") (pinfunction "5_5") (pintype "bidirectional"))
    )
    (net (code "122") (name "unconnected-(U7-3V3_EN-Pad37)") (class "Default")
      (node (ref "U7") (pin "37") (pinfunction "3V3_EN_37") (pintype "input"))
    )
    (net (code "123") (name "unconnected-(U7-ADC_REF-Pad35)") (class "Default")
      (node (ref "U7") (pin "35") (pinfunction "ADC_REF_35") (pintype "input"))
    )
    (net (code "124") (name "unconnected-(U7-RUN-Pad30)") (class "Default")
      (node (ref "U7") (pin "30") (pinfunction "RUN_30") (pintype "input"))
    )
    (net (code "125") (name "unconnected-(U7-SWCLK-Pad41)") (class "Default")
      (node (ref "U7") (pin "41") (pinfunction "SWCLK_41") (pintype "input"))
    )
    (net (code "126") (name "unconnected-(U7-SWDIO-Pad43)") (class "Default")
      (node (ref "U7") (pin "43") (pinfunction "SWDIO_43") (pintype "bidirectional"))
    )
  )
)
